# SCH__ESP32_NES__2022-10-13.net
KiCad netlist of a schematic drawn in EasyEDA
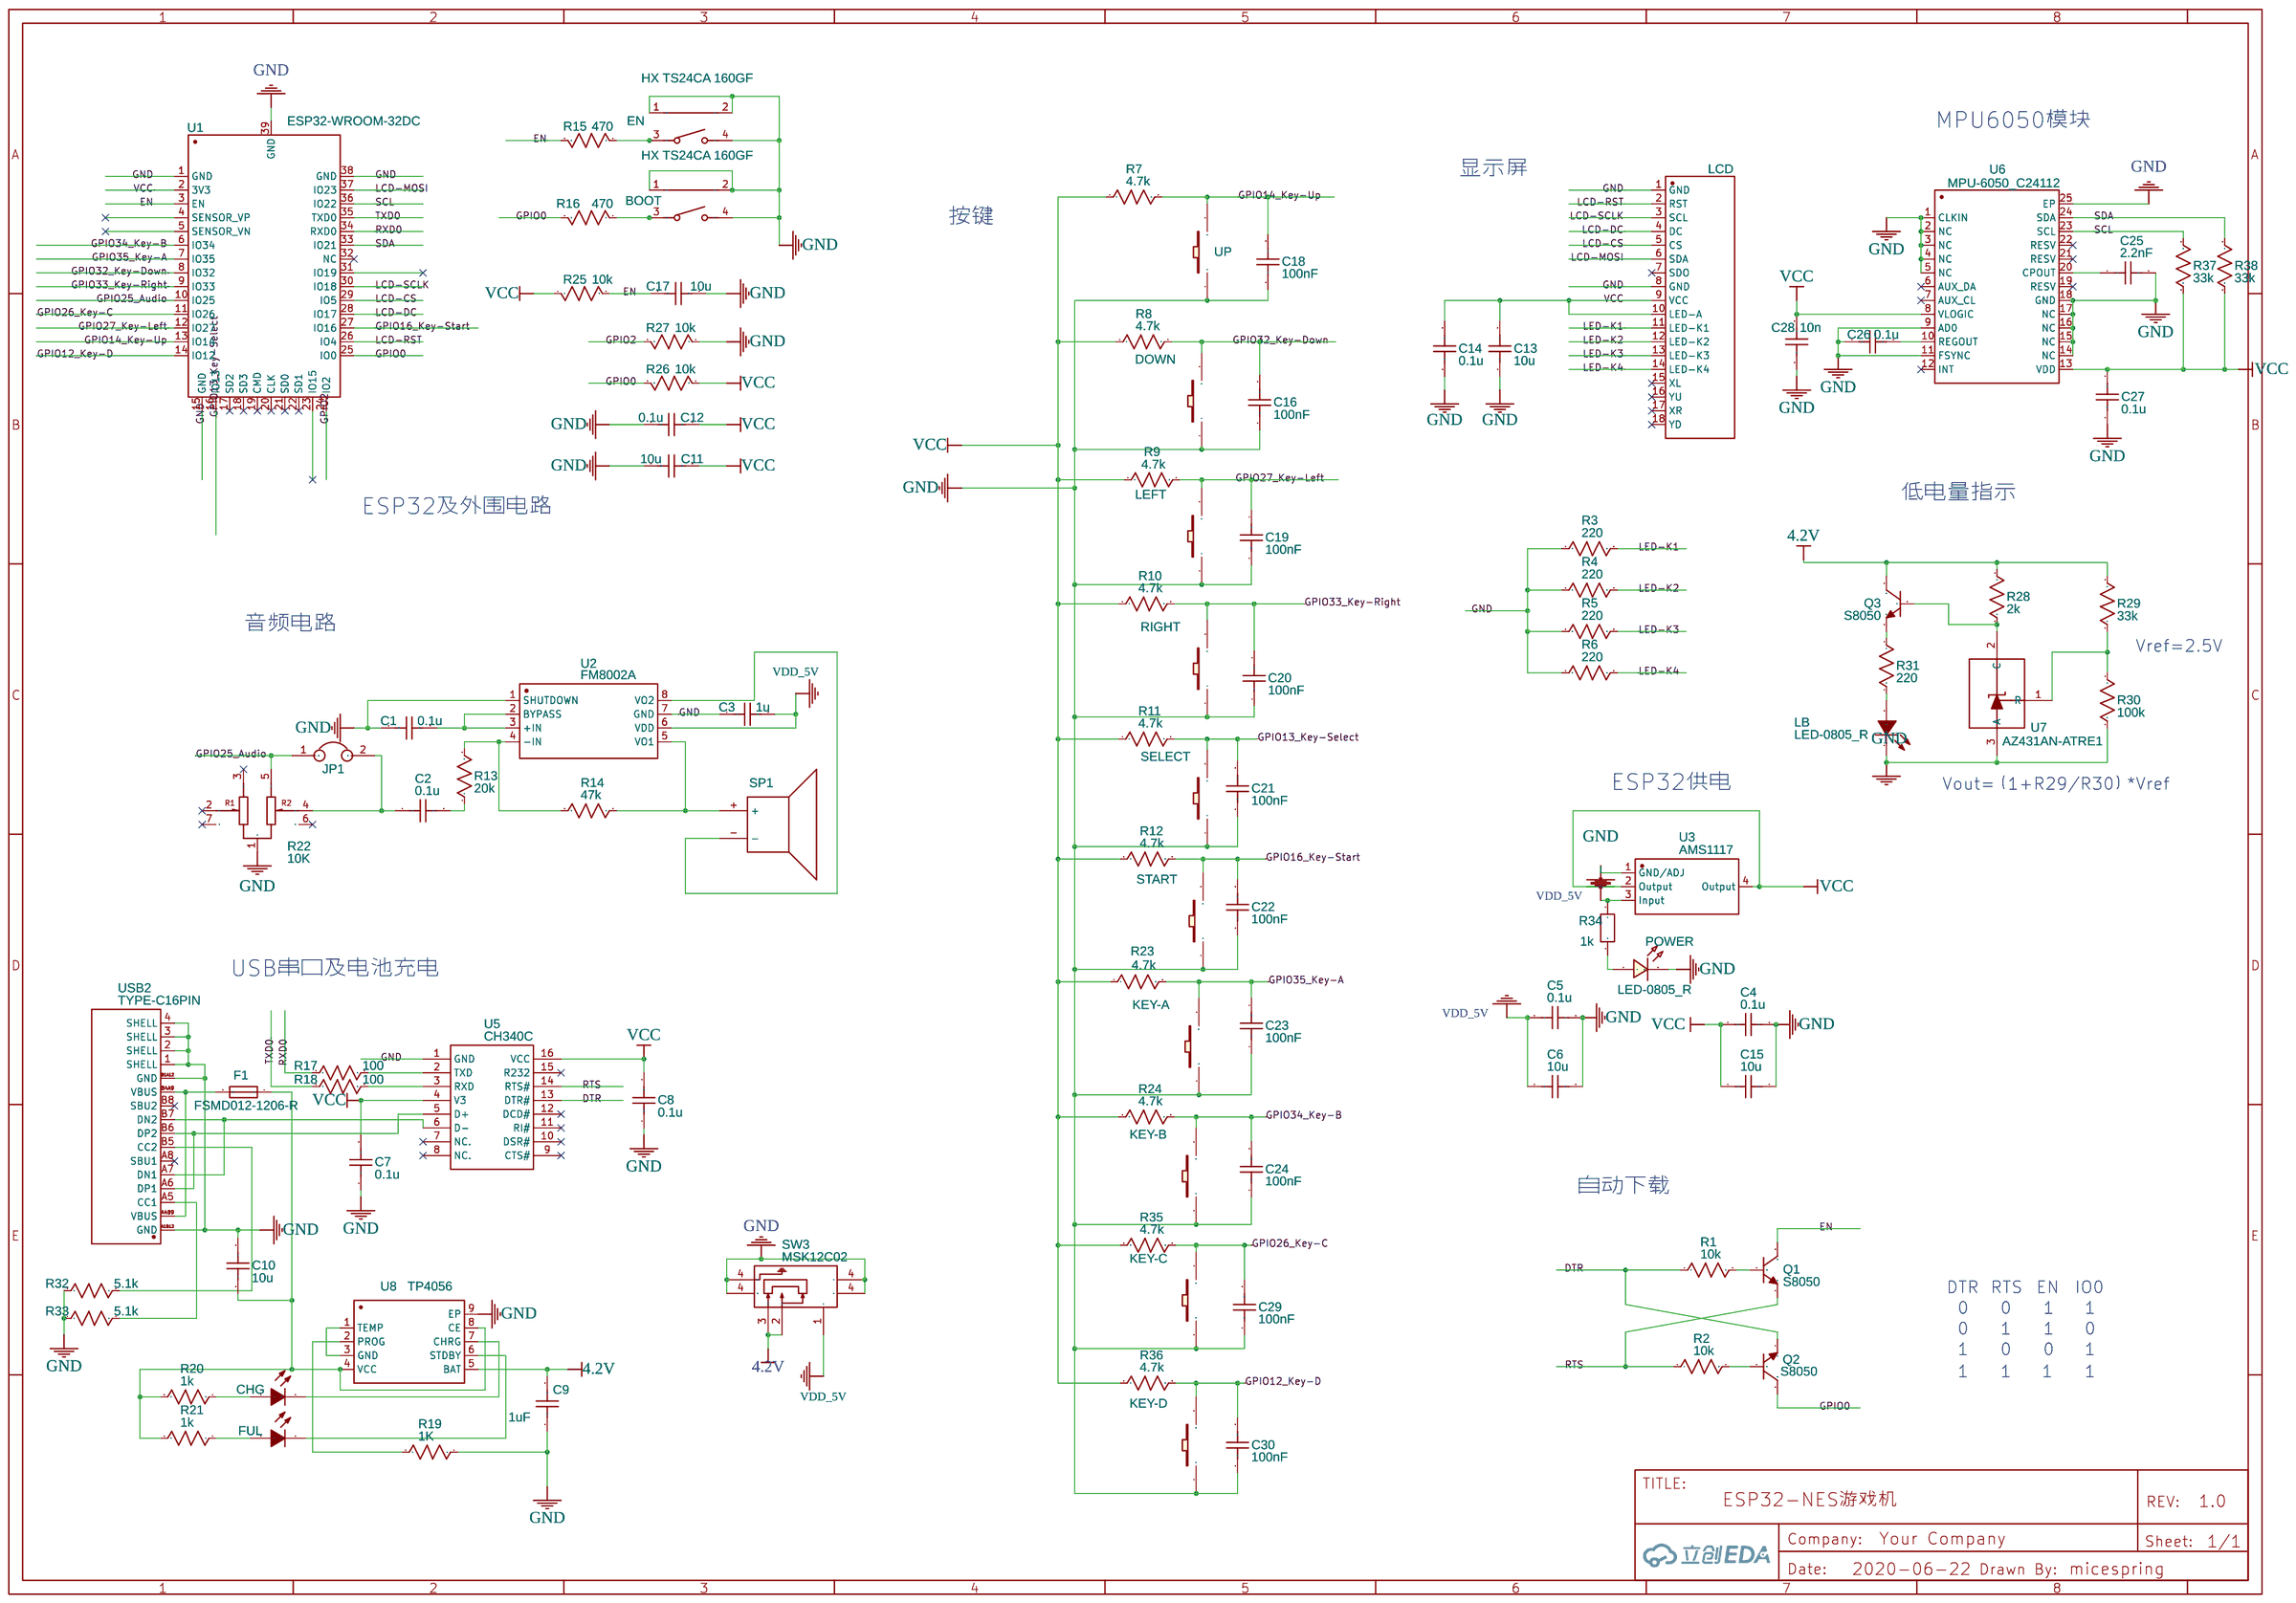
[diagram p0: 主板]
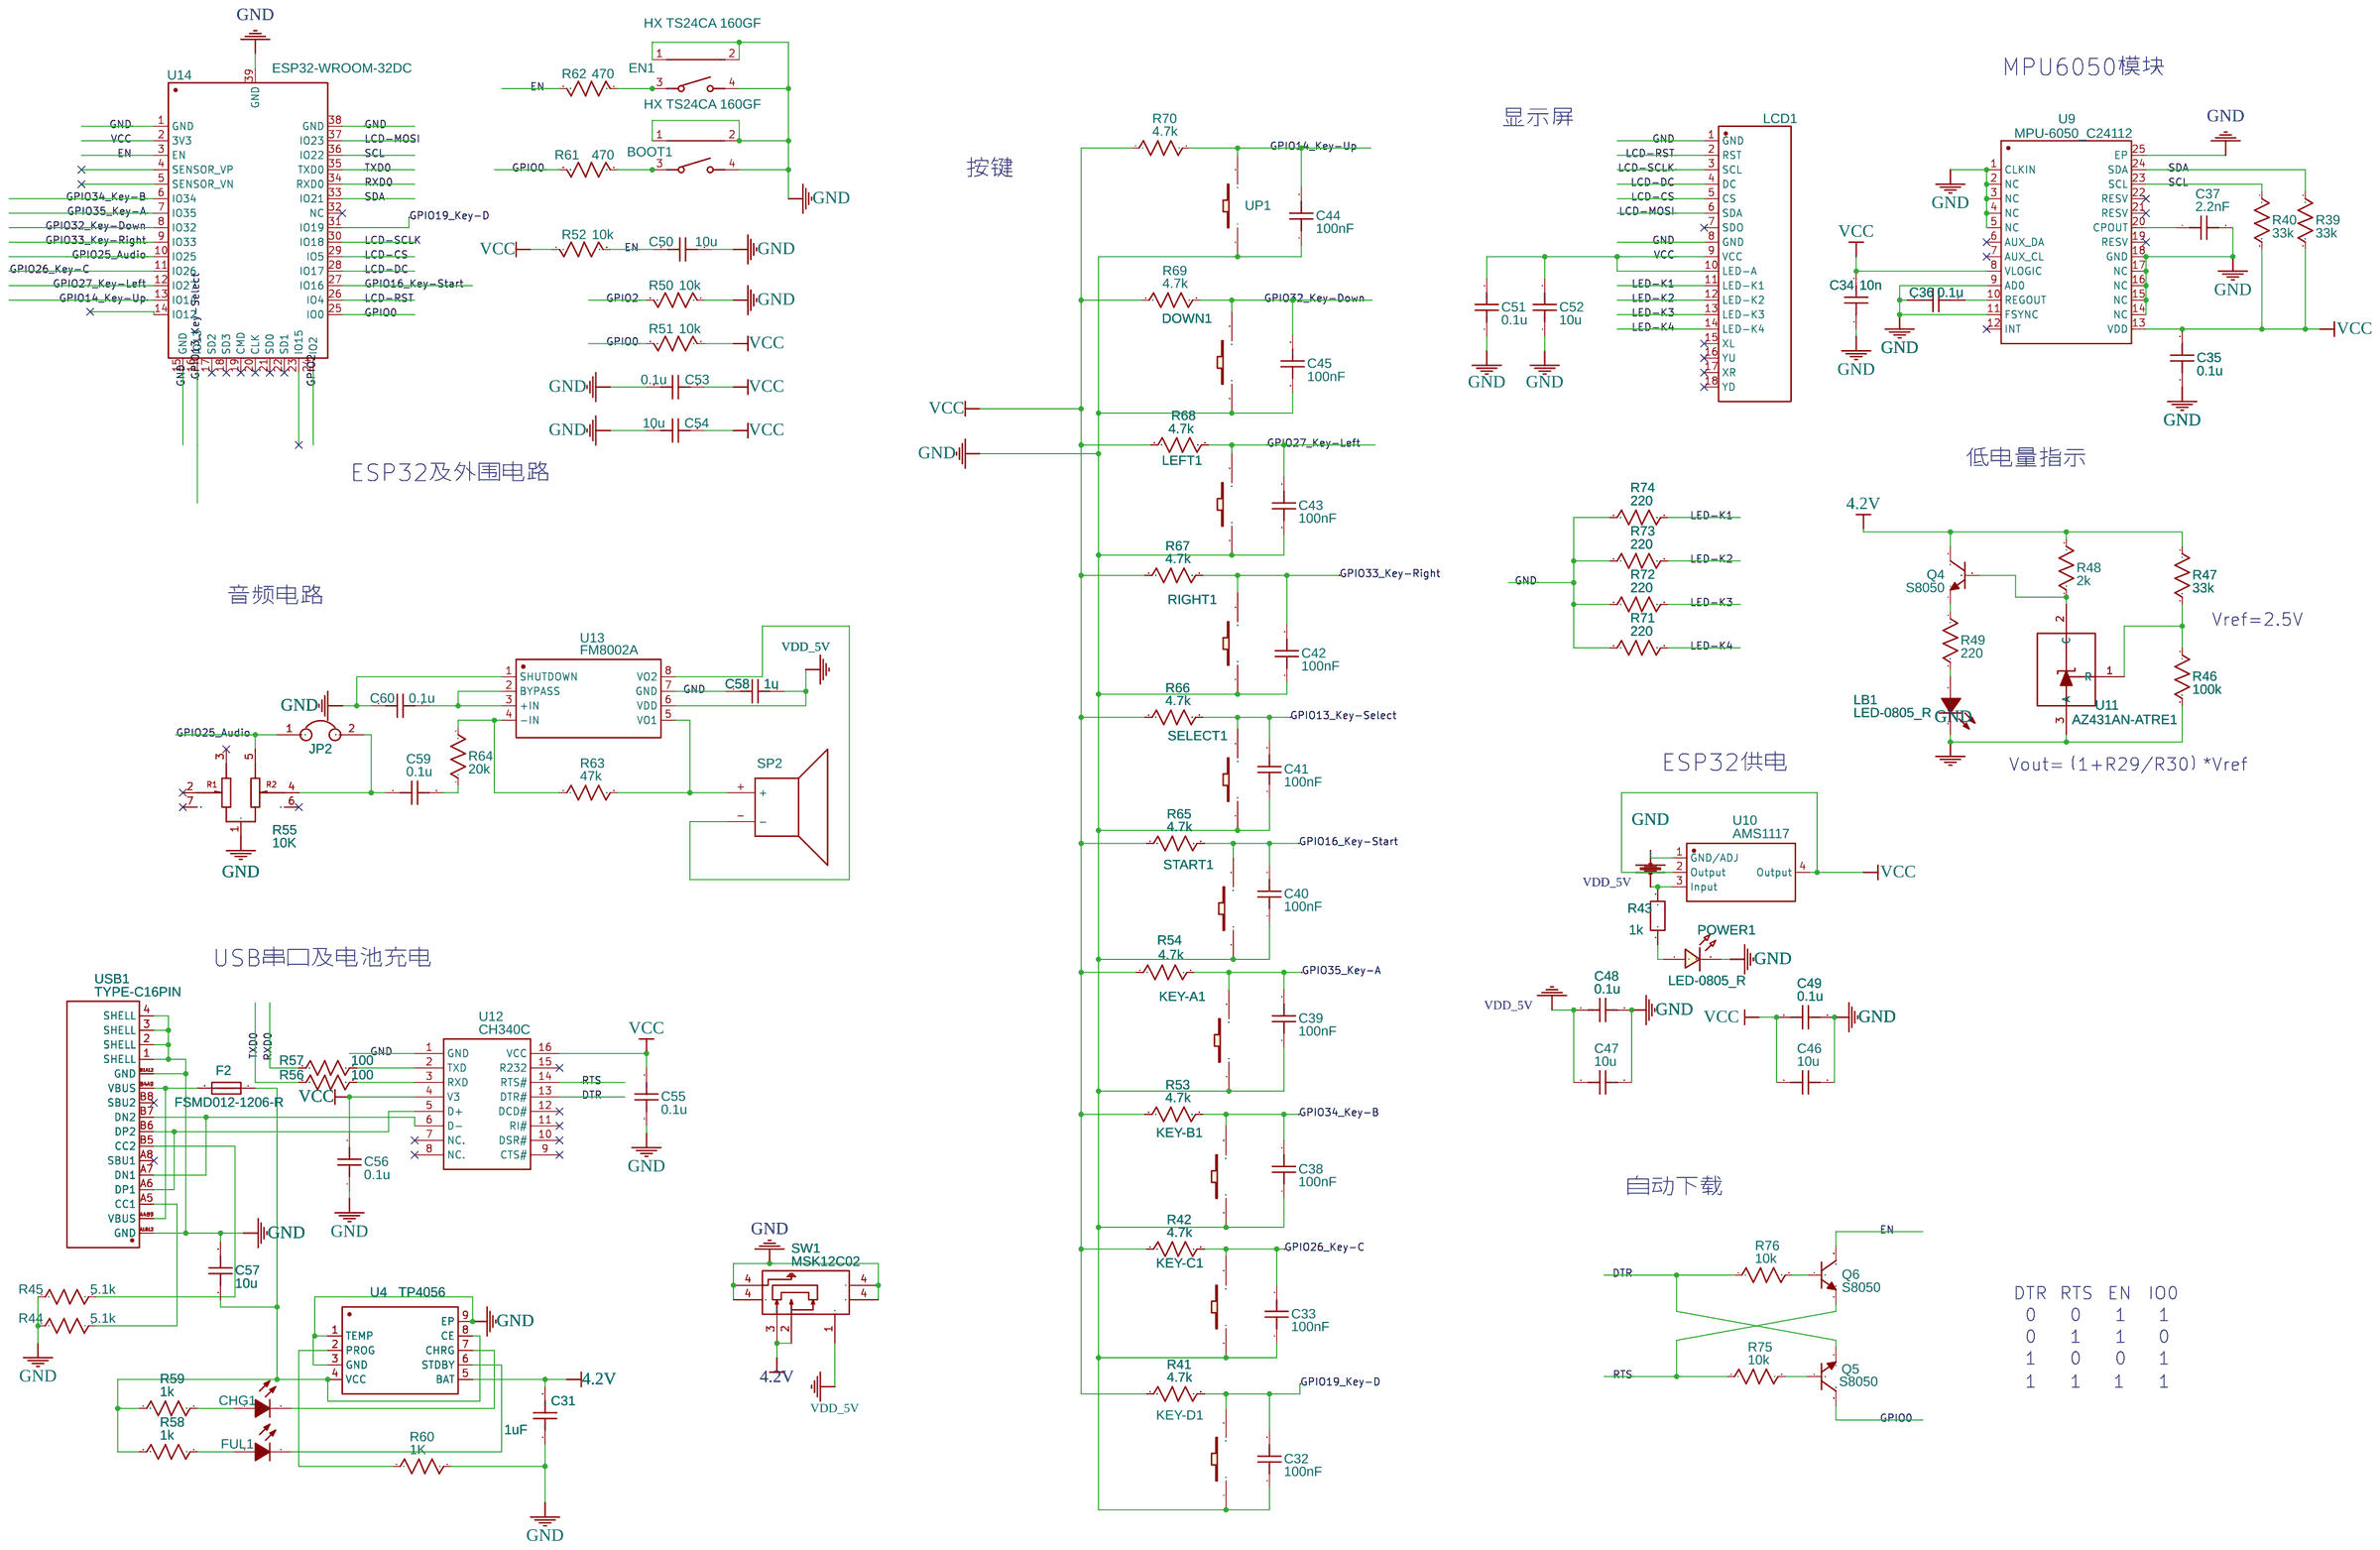
[diagram p1: 新主板]

(export (version "E")
  (design (tool "Eeschema 10.0.6"))
  (components
    (comp (ref "BOOT")
      (value "HX TS24CA 160GF")
      (fields
        (field (name "BOM_Manufacturer Part") "HX TS24CA 160gf")
        (field (name "BOM_Supplier Part") "C5143620")
      )
      (libsource (lib "") (part "HX TS24CA 160GF_1"))
    )
    (comp (ref "C1")
      (value "0.1u")
      (fields
        (field (name "BOM_Manufacturer Part") "TCC0805X7R104K500DT")
        (field (name "BOM_Supplier Part") "C282732")
      )
      (libsource (lib "") (part "C_0805_US_2"))
    )
    (comp (ref "C2")
      (value "0.1u")
      (fields
        (field (name "BOM_Manufacturer Part") "TCC0805X7R104K500DT")
        (field (name "BOM_Supplier Part") "C282732")
      )
      (libsource (lib "") (part "C_0805_US_2"))
    )
    (comp (ref "C3")
      (value "1u")
      (fields
        (field (name "BOM_Manufacturer Part") "0805B105K250NT")
        (field (name "BOM_Supplier Part") "C89190")
      )
      (libsource (lib "") (part "C_0805_US_2"))
    )
    (comp (ref "C4") (value "0.1u") (libsource (lib "") (part "C_0805_US_2")))
    (comp (ref "C5") (value "0.1u") (libsource (lib "") (part "C_0805_US_2")))
    (comp (ref "C6") (value "10u") (libsource (lib "") (part "C_0603_US_1")))
    (comp (ref "C7")
      (value "0.1u")
      (fields
        (field (name "BOM_Manufacturer Part") "TCC0805X7R104K500DT")
        (field (name "BOM_Supplier Part") "C282732")
      )
      (libsource (lib "") (part "C_0805_US_1"))
    )
    (comp (ref "C8")
      (value "0.1u")
      (fields
        (field (name "BOM_Manufacturer Part") "TCC0805X7R104K500DT")
        (field (name "BOM_Supplier Part") "C282732")
      )
      (libsource (lib "") (part "C_0805_US_1"))
    )
    (comp (ref "C9") (value "1uF") (libsource (lib "") (part "C_0603_US")))
    (comp (ref "C10")
      (value "10u")
      (fields
        (field (name "BOM_Manufacturer Part") "CL31A106KAHNNNE")
        (field (name "BOM_Supplier Part") "C9807")
      )
      (libsource (lib "") (part "Cap_1206_US"))
    )
    (comp (ref "C11")
      (value "10u")
      (fields
        (field (name "BOM_Manufacturer Part") "CL31A106KAHNNNE")
        (field (name "BOM_Supplier Part") "C9807")
      )
      (libsource (lib "") (part "C_0805_US"))
    )
    (comp (ref "C12")
      (value "0.1u")
      (fields
        (field (name "BOM_Manufacturer Part") "TCC0805X7R104K500DT")
        (field (name "BOM_Supplier Part") "C282732")
      )
      (libsource (lib "") (part "C_0805_US"))
    )
    (comp (ref "C13")
      (value "10u")
      (fields
        (field (name "BOM_Manufacturer Part") "CC0805KRX5R6BB106")
        (field (name "BOM_Supplier Part") "C272880")
      )
      (libsource (lib "") (part "Cap_0805_US"))
    )
    (comp (ref "C14")
      (value "0.1u")
      (fields
        (field (name "BOM_Manufacturer Part") "TCC0805X7R104K500DT")
        (field (name "BOM_Supplier Part") "C282732")
      )
      (libsource (lib "") (part "Cap_0805_US"))
    )
    (comp (ref "C15") (value "10u") (libsource (lib "") (part "C_0603_US_1")))
    (comp (ref "C16") (value "100nF") (libsource (lib "") (part "C_0603_US")))
    (comp (ref "C17")
      (value "10u")
      (fields
        (field (name "BOM_Manufacturer Part") "TCC0805X7R104K500DT")
        (field (name "BOM_Supplier Part") "C282732")
      )
      (libsource (lib "") (part "C_0805_US_3"))
    )
    (comp (ref "C18") (value "100nF") (libsource (lib "") (part "C_0603_US")))
    (comp (ref "C19") (value "100nF") (libsource (lib "") (part "C_0603_US_2")))
    (comp (ref "C20") (value "100nF") (libsource (lib "") (part "C_0603_US")))
    (comp (ref "C21") (value "100nF") (libsource (lib "") (part "C_0603_US")))
    (comp (ref "C22") (value "100nF") (libsource (lib "") (part "C_0603_US")))
    (comp (ref "C23") (value "100nF") (libsource (lib "") (part "C_0603_US")))
    (comp (ref "C24") (value "100nF") (libsource (lib "") (part "C_0603_US")))
    (comp (ref "C25") (value "2.2nF") (libsource (lib "") (part "C_0603_US_1")))
    (comp (ref "C26") (value "0.1u") (libsource (lib "") (part "C_0603_US_1")))
    (comp (ref "C27") (value "0.1u") (libsource (lib "") (part "C_0603_US")))
    (comp (ref "C28") (value "10n") (libsource (lib "") (part "C_0603_US")))
    (comp (ref "C29") (value "100nF") (libsource (lib "") (part "C_0603_US")))
    (comp (ref "C30") (value "100nF") (libsource (lib "") (part "C_0603_US")))
    (comp (ref "CHG")
      (value "17-21/BHC-XL2M2TY/3T")
      (fields (field (name "BOM_Supplier Part") "C72035"))
      (libsource (lib "") (part "Unknown_195_195"))
    )
    (comp (ref "DOWN")
      (value "K2-1817UQ-C4SW-01")
      (fields (field (name "BOM_Supplier Part") "C128939"))
      (libsource (lib "") (part "K2-1817UQ-C4SW-01_1"))
    )
    (comp (ref "EN")
      (value "HX TS24CA 160GF")
      (fields
        (field (name "BOM_Manufacturer Part") "HX TS24CA 160gf")
        (field (name "BOM_Supplier Part") "C5143620")
      )
      (libsource (lib "") (part "HX TS24CA 160GF"))
    )
    (comp (ref "F1")
      (value "FSMD012-1206-R")
      (fields (field (name "BOM_Supplier Part") "C220144"))
      (libsource (lib "") (part "FSMD012-1206-R"))
    )
    (comp (ref "FUL")
      (value "17-21/BHC-XL2M2TY/3T")
      (fields
        (field (name "BOM_Manufacturer Part") "FC-2012UGK-520D5")
        (field (name "BOM_Supplier Part") "C84260")
      )
      (libsource (lib "") (part "Unknown_195_225"))
    )
    (comp (ref "JP1") (value "JUMPER") (libsource (lib "") (part "JUMPER")))
    (comp (ref "KEY-A")
      (value "K2-1817UQ-C4SW-01")
      (fields (field (name "BOM_Supplier Part") "C128939"))
      (libsource (lib "") (part "K2-1817UQ-C4SW-01_2"))
    )
    (comp (ref "KEY-B")
      (value "K2-1817UQ-C4SW-01")
      (fields (field (name "BOM_Supplier Part") "C128939"))
      (libsource (lib "") (part "K2-1817UQ-C4SW-01_4"))
    )
    (comp (ref "KEY-C")
      (value "K2-1817UQ-C4SW-01")
      (fields (field (name "BOM_Supplier Part") "C128939"))
      (libsource (lib "") (part "K2-1817UQ-C4SW-01_5"))
    )
    (comp (ref "KEY-D")
      (value "K2-1817UQ-C4SW-01")
      (fields (field (name "BOM_Supplier Part") "C128939"))
      (libsource (lib "") (part "K2-1817UQ-C4SW-01_8"))
    )
    (comp (ref "LB")
      (value "LED-0805_R")
      (fields
        (field (name "BOM_Manufacturer Part") "17-21SURC/S530-A3/TR8")
        (field (name "BOM_Supplier Part") "C72037")
      )
      (libsource (lib "") (part "LED-0805_R"))
    )
    (comp (ref "LCD")
      (value "TFT_2.4_18P_SPI_ILI9341_240X320_65K_S")
      (libsource (lib "") (part "TFT_2.4_18P_SPI_ILI9341_240X320_65K_S"))
    )
    (comp (ref "LEFT")
      (value "K2-1817UQ-C4SW-01")
      (fields (field (name "BOM_Supplier Part") "C128939"))
      (libsource (lib "") (part "K2-1817UQ-C4SW-01_7"))
    )
    (comp (ref "POWER")
      (value "LED-0805_R")
      (fields
        (field (name "BOM_Manufacturer Part") "17-21SURC/S530-A3/TR8")
        (field (name "BOM_Supplier Part") "C72037")
      )
      (libsource (lib "") (part "LED-0805_R_1"))
    )
    (comp (ref "Q1")
      (value "S8050")
      (fields
        (field (name "BOM_Manufacturer Part") "2n3904S-RTK/PS")
        (field (name "BOM_Supplier Part") "C18536")
      )
      (libsource (lib "") (part "2N3904(SOT-23)_1"))
    )
    (comp (ref "Q2")
      (value "S8050")
      (fields
        (field (name "BOM_Manufacturer Part") "2n3904S-RTK/PS")
        (field (name "BOM_Supplier Part") "C18536")
      )
      (libsource (lib "") (part "2N3904(SOT-23)_2"))
    )
    (comp (ref "Q3")
      (value "S8050")
      (fields
        (field (name "BOM_Manufacturer Part") "2n3904S-RTK/PS")
        (field (name "BOM_Supplier Part") "C18536")
      )
      (libsource (lib "") (part "2N3904(SOT-23)"))
    )
    (comp (ref "R1")
      (value "10k")
      (fields
        (field (name "BOM_Manufacturer Part") "RTT051002FTP")
        (field (name "BOM_Supplier Part") "C103904")
      )
      (libsource (lib "") (part "R_0805_US_1"))
    )
    (comp (ref "R2")
      (value "10k")
      (fields
        (field (name "BOM_Manufacturer Part") "RTT051002FTP")
        (field (name "BOM_Supplier Part") "C103904")
      )
      (libsource (lib "") (part "R_0805_US_1"))
    )
    (comp (ref "R3")
      (value "220")
      (fields
        (field (name "BOM_Manufacturer Part") "RC0805FR-07220RL")
        (field (name "BOM_Supplier Part") "C114519")
      )
      (libsource (lib "") (part "R_0805_US_1"))
    )
    (comp (ref "R4")
      (value "220")
      (fields
        (field (name "BOM_Manufacturer Part") "RC0805FR-07220RL")
        (field (name "BOM_Supplier Part") "C114519")
      )
      (libsource (lib "") (part "R_0805_US_1"))
    )
    (comp (ref "R5")
      (value "220")
      (fields
        (field (name "BOM_Manufacturer Part") "RC0805FR-07220RL")
        (field (name "BOM_Supplier Part") "C114519")
      )
      (libsource (lib "") (part "R_0805_US_1"))
    )
    (comp (ref "R6")
      (value "220")
      (fields
        (field (name "BOM_Manufacturer Part") "RC0805FR-07220RL")
        (field (name "BOM_Supplier Part") "C114519")
      )
      (libsource (lib "") (part "R_0805_US_1"))
    )
    (comp (ref "R7")
      (value "4.7k")
      (fields
        (field (name "BOM_Manufacturer Part") "0805W8F4701T5E")
        (field (name "BOM_Supplier Part") "C17673")
      )
      (libsource (lib "") (part "R_0805_US_1"))
    )
    (comp (ref "R8")
      (value "4.7k")
      (fields
        (field (name "BOM_Manufacturer Part") "0805W8F4701T5E")
        (field (name "BOM_Supplier Part") "C17673")
      )
      (libsource (lib "") (part "R_0805_US_1"))
    )
    (comp (ref "R9")
      (value "4.7k")
      (fields
        (field (name "BOM_Manufacturer Part") "0805W8F4701T5E")
        (field (name "BOM_Supplier Part") "C17673")
      )
      (libsource (lib "") (part "R_0805_US_1"))
    )
    (comp (ref "R10")
      (value "4.7k")
      (fields
        (field (name "BOM_Manufacturer Part") "0805W8F4701T5E")
        (field (name "BOM_Supplier Part") "C17673")
      )
      (libsource (lib "") (part "R_0805_US_1"))
    )
    (comp (ref "R11")
      (value "4.7k")
      (fields
        (field (name "BOM_Manufacturer Part") "0805W8F4701T5E")
        (field (name "BOM_Supplier Part") "C17673")
      )
      (libsource (lib "") (part "R_0805_US_1"))
    )
    (comp (ref "R12")
      (value "4.7k")
      (fields
        (field (name "BOM_Manufacturer Part") "0805W8F4701T5E")
        (field (name "BOM_Supplier Part") "C17673")
      )
      (libsource (lib "") (part "R_0805_US_1"))
    )
    (comp (ref "R13")
      (value "20k")
      (fields
        (field (name "BOM_Manufacturer Part") "RS-05K2002FT")
        (field (name "BOM_Supplier Part") "C136576")
      )
      (libsource (lib "") (part "R_0805_US_3"))
    )
    (comp (ref "R14")
      (value "47k")
      (fields
        (field (name "BOM_Manufacturer Part") "RS-05K4702FT")
        (field (name "BOM_Supplier Part") "C136580")
      )
      (libsource (lib "") (part "R_0805_US_1"))
    )
    (comp (ref "R15")
      (value "470")
      (fields
        (field (name "BOM_Manufacturer Part") "RC0805FR-07470RL")
        (field (name "BOM_Supplier Part") "C114564")
      )
      (libsource (lib "") (part "R_0805_US"))
    )
    (comp (ref "R16")
      (value "470")
      (fields
        (field (name "BOM_Manufacturer Part") "RC0805FR-07470RL")
        (field (name "BOM_Supplier Part") "C114564")
      )
      (libsource (lib "") (part "R_0805_US"))
    )
    (comp (ref "R17")
      (value "100")
      (fields
        (field (name "BOM_Manufacturer Part") "CR0805F81000G")
        (field (name "BOM_Supplier Part") "C101403")
      )
      (libsource (lib "") (part "R_0805_US_1"))
    )
    (comp (ref "R18")
      (value "100")
      (fields
        (field (name "BOM_Manufacturer Part") "CR0805F81000G")
        (field (name "BOM_Supplier Part") "C101403")
      )
      (libsource (lib "") (part "R_0805_US_1"))
    )
    (comp (ref "R19")
      (value "1K")
      (fields
        (field (name "BOM_Manufacturer Part") "RS-05K3301FT")
        (field (name "BOM_Supplier Part") "C294703")
      )
      (libsource (lib "") (part "Res_0805(1/8W)_US_1"))
    )
    (comp (ref "R20")
      (value "1k")
      (fields
        (field (name "BOM_Manufacturer Part") "0805W8F1001T5E")
        (field (name "BOM_Supplier Part") "C17513")
      )
      (libsource (lib "") (part "Res_0805(1/8W)_US_2"))
    )
    (comp (ref "R21")
      (value "1k")
      (fields
        (field (name "BOM_Manufacturer Part") "0805W8F1001T5E")
        (field (name "BOM_Supplier Part") "C17513")
      )
      (libsource (lib "") (part "Res_0805(1/8W)_US_2"))
    )
    (comp (ref "R22")
      (value "10K")
      (fields
        (field (name "BOM_Manufacturer Part") "RK10J12E002L")
        (field (name "BOM_Supplier Part") "C231765")
      )
      (libsource (lib "") (part "RK10J12E002L"))
    )
    (comp (ref "R23")
      (value "4.7k")
      (fields
        (field (name "BOM_Manufacturer Part") "0805W8F4701T5E")
        (field (name "BOM_Supplier Part") "C17673")
      )
      (libsource (lib "") (part "R_0805_US_1"))
    )
    (comp (ref "R24")
      (value "4.7k")
      (fields
        (field (name "BOM_Manufacturer Part") "0805W8F4701T5E")
        (field (name "BOM_Supplier Part") "C17673")
      )
      (libsource (lib "") (part "R_0805_US_1"))
    )
    (comp (ref "R25")
      (value "10k")
      (fields
        (field (name "BOM_Manufacturer Part") "RTT051002FTP")
        (field (name "BOM_Supplier Part") "C103904")
      )
      (libsource (lib "") (part "R_0805_US_2"))
    )
    (comp (ref "R26")
      (value "10k")
      (fields
        (field (name "BOM_Manufacturer Part") "RTT051002FTP")
        (field (name "BOM_Supplier Part") "C103904")
      )
      (libsource (lib "") (part "R_0805_US"))
    )
    (comp (ref "R27")
      (value "10k")
      (fields
        (field (name "BOM_Manufacturer Part") "RTT051002FTP")
        (field (name "BOM_Supplier Part") "C103904")
      )
      (libsource (lib "") (part "R_0805_US"))
    )
    (comp (ref "R28")
      (value "2k")
      (fields
        (field (name "BOM_Manufacturer Part") "0805W8F2001T5E")
        (field (name "BOM_Supplier Part") "C17604")
      )
      (libsource (lib "") (part "Res_0805(1/8W)_US"))
    )
    (comp (ref "R29")
      (value "33k")
      (fields
        (field (name "BOM_Manufacturer Part") "RS-05K3302FT")
        (field (name "BOM_Supplier Part") "C139883")
      )
      (libsource (lib "") (part "Res_0805(1/8W)_US"))
    )
    (comp (ref "R30")
      (value "100k")
      (fields
        (field (name "BOM_Manufacturer Part") "0805W8F1003T5E")
        (field (name "BOM_Supplier Part") "C149504")
      )
      (libsource (lib "") (part "Res_0805(1/8W)_US"))
    )
    (comp (ref "R31")
      (value "220")
      (fields
        (field (name "BOM_Manufacturer Part") "RC0805FR-07220RL")
        (field (name "BOM_Supplier Part") "C114519")
      )
      (libsource (lib "") (part "Res_0805(1/8W)_US"))
    )
    (comp (ref "R32")
      (value "5.1k")
      (fields
        (field (name "BOM_Manufacturer Part") "CR0805F81000G")
        (field (name "BOM_Supplier Part") "C101403")
      )
      (libsource (lib "") (part "R_0805_US_1"))
    )
    (comp (ref "R33")
      (value "5.1k")
      (fields
        (field (name "BOM_Manufacturer Part") "CR0805F81000G")
        (field (name "BOM_Supplier Part") "C101403")
      )
      (libsource (lib "") (part "R_0805_US_1"))
    )
    (comp (ref "R34") (value "1k") (libsource (lib "") (part "R_0805_EU")))
    (comp (ref "R35")
      (value "4.7k")
      (fields
        (field (name "BOM_Manufacturer Part") "0805W8F4701T5E")
        (field (name "BOM_Supplier Part") "C17673")
      )
      (libsource (lib "") (part "R_0805_US_1"))
    )
    (comp (ref "R36")
      (value "4.7k")
      (fields
        (field (name "BOM_Manufacturer Part") "0805W8F4701T5E")
        (field (name "BOM_Supplier Part") "C17673")
      )
      (libsource (lib "") (part "R_0805_US_1"))
    )
    (comp (ref "R37")
      (value "33k")
      (fields
        (field (name "BOM_Manufacturer Part") "RS-05K3302FT")
        (field (name "BOM_Supplier Part") "C139883")
      )
      (libsource (lib "") (part "Res_0805(1/8W)_US"))
    )
    (comp (ref "R38")
      (value "33k")
      (fields
        (field (name "BOM_Manufacturer Part") "RS-05K3302FT")
        (field (name "BOM_Supplier Part") "C139883")
      )
      (libsource (lib "") (part "Res_0805(1/8W)_US"))
    )
    (comp (ref "RIGHT")
      (value "K2-1817UQ-C4SW-01")
      (fields (field (name "BOM_Supplier Part") "C128939"))
      (libsource (lib "") (part "K2-1817UQ-C4SW-01_6"))
    )
    (comp (ref "SELECT")
      (value "K2-1817UQ-C4SW-01")
      (fields (field (name "BOM_Supplier Part") "C128939"))
      (libsource (lib "") (part "K2-1817UQ-C4SW-01_9"))
    )
    (comp (ref "SP1")
      (value "SPEAKER-FS-2308-P9.2")
      (fields (field (name "BOM_Supplier Part") "C482322"))
      (libsource (lib "") (part "SPEAKER-FS-2308-P9.2"))
    )
    (comp (ref "START")
      (value "K2-1817UQ-C4SW-01")
      (fields (field (name "BOM_Supplier Part") "C128939"))
      (libsource (lib "") (part "K2-1817UQ-C4SW-01_3"))
    )
    (comp (ref "SW3")
      (value "MSK12C02")
      (fields (field (name "BOM_Supplier Part") "C431540"))
      (libsource (lib "") (part "MSK12C02"))
    )
    (comp (ref "U1")
      (value "ESP32-WROOM-32DC")
      (fields (field (name "BOM_Supplier Part") "C473013"))
      (libsource (lib "") (part "ESP32-WROOM-32DC"))
    )
    (comp (ref "U2")
      (value "FM8002A")
      (fields (field (name "BOM_Supplier Part") "C94625"))
      (libsource (lib "") (part "FM8002A"))
    )
    (comp (ref "U3")
      (value "AMS1117")
      (fields
        (field (name "BOM_Manufacturer Part") "AMS1117-3.3")
        (field (name "BOM_Supplier Part") "C369933")
      )
      (libsource (lib "") (part "AMS1117-3.3_C369933"))
    )
    (comp (ref "U5")
      (value "CH340C")
      (fields (field (name "BOM_Supplier Part") "C84681"))
      (libsource (lib "") (part "CH340C"))
    )
    (comp (ref "U6")
      (value "MPU-6050_C24112")
      (fields (field (name "BOM_Manufacturer Part") "MPU-6050") (field (name "BOM_Supplier Part") "C24112"))
      (libsource (lib "") (part "MPU-6050_C24112"))
    )
    (comp (ref "U7")
      (value "AZ431AN-ATRE1")
      (fields (field (name "BOM_Supplier Part") "C84138"))
      (libsource (lib "") (part "AZ431AN-ATRE1"))
    )
    (comp (ref "U8")
      (value "TP4056")
      (fields (field (name "BOM_Supplier Part") "C725790"))
      (libsource (lib "") (part "TP4056_C725790"))
    )
    (comp (ref "UP")
      (value "K2-1817UQ-C4SW-01")
      (fields (field (name "BOM_Supplier Part") "C128939"))
      (libsource (lib "") (part "K2-1817UQ-C4SW-01"))
    )
    (comp (ref "USB2")
      (value "TYPE-C16PIN")
      (fields (field (name "BOM_Supplier Part") "C393939"))
      (libsource (lib "") (part "TYPE-C16PIN"))
    )
    (comp (ref "BOOT1")
      (value "HX TS24CA 160GF")
      (fields
        (field (name "BOM_Manufacturer Part") "HX TS24CA 160gf")
        (field (name "BOM_Supplier Part") "C5143620")
      )
      (libsource (lib "") (part "HX TS24CA 160GF"))
    )
    (comp (ref "C31") (value "1uF") (libsource (lib "") (part "C_0603_US_2")))
    (comp (ref "C32") (value "100nF") (libsource (lib "") (part "C_0603_US_2")))
    (comp (ref "C33") (value "100nF") (libsource (lib "") (part "C_0603_US_2")))
    (comp (ref "C34") (value "10n") (libsource (lib "") (part "C_0603_US_2")))
    (comp (ref "C35") (value "0.1u") (libsource (lib "") (part "C_0603_US_2")))
    (comp (ref "C36") (value "0.1u") (libsource (lib "") (part "C_0603_US")))
    (comp (ref "C37") (value "2.2nF") (libsource (lib "") (part "C_0603_US")))
    (comp (ref "C38") (value "100nF") (libsource (lib "") (part "C_0603_US_2")))
    (comp (ref "C39") (value "100nF") (libsource (lib "") (part "C_0603_US_2")))
    (comp (ref "C40") (value "100nF") (libsource (lib "") (part "C_0603_US_2")))
    (comp (ref "C41") (value "100nF") (libsource (lib "") (part "C_0603_US_2")))
    (comp (ref "C42") (value "100nF") (libsource (lib "") (part "C_0603_US_2")))
    (comp (ref "C43") (value "100nF") (libsource (lib "") (part "C_0603_US_1")))
    (comp (ref "C44") (value "100nF") (libsource (lib "") (part "C_0603_US_2")))
    (comp (ref "C45") (value "100nF") (libsource (lib "") (part "C_0603_US_2")))
    (comp (ref "C46") (value "10u") (libsource (lib "") (part "C_0603_US")))
    (comp (ref "C47") (value "10u") (libsource (lib "") (part "C_0603_US")))
    (comp (ref "C48") (value "0.1u") (libsource (lib "") (part "C_0805_US")))
    (comp (ref "C49") (value "0.1u") (libsource (lib "") (part "C_0805_US")))
    (comp (ref "C50")
      (value "10u")
      (fields
        (field (name "BOM_Manufacturer Part") "TCC0805X7R104K500DT")
        (field (name "BOM_Supplier Part") "C282732")
      )
      (libsource (lib "") (part "C_0805_US_1"))
    )
    (comp (ref "C51")
      (value "0.1u")
      (fields
        (field (name "BOM_Manufacturer Part") "TCC0805X7R104K500DT")
        (field (name "BOM_Supplier Part") "C282732")
      )
      (libsource (lib "") (part "Cap_0805_US"))
    )
    (comp (ref "C52")
      (value "10u")
      (fields
        (field (name "BOM_Manufacturer Part") "CC0805KRX5R6BB106")
        (field (name "BOM_Supplier Part") "C272880")
      )
      (libsource (lib "") (part "Cap_0805_US"))
    )
    (comp (ref "C53")
      (value "0.1u")
      (fields
        (field (name "BOM_Manufacturer Part") "TCC0805X7R104K500DT")
        (field (name "BOM_Supplier Part") "C282732")
      )
      (libsource (lib "") (part "C_0805_US_2"))
    )
    (comp (ref "C54")
      (value "10u")
      (fields
        (field (name "BOM_Manufacturer Part") "CL31A106KAHNNNE")
        (field (name "BOM_Supplier Part") "C9807")
      )
      (libsource (lib "") (part "C_0805_US_2"))
    )
    (comp (ref "C55")
      (value "0.1u")
      (fields
        (field (name "BOM_Manufacturer Part") "TCC0805X7R104K500DT")
        (field (name "BOM_Supplier Part") "C282732")
      )
      (libsource (lib "") (part "C_0805_US_3"))
    )
    (comp (ref "C56")
      (value "0.1u")
      (fields
        (field (name "BOM_Manufacturer Part") "TCC0805X7R104K500DT")
        (field (name "BOM_Supplier Part") "C282732")
      )
      (libsource (lib "") (part "C_0805_US_3"))
    )
    (comp (ref "C57")
      (value "10u")
      (fields
        (field (name "BOM_Manufacturer Part") "CL31A106KAHNNNE")
        (field (name "BOM_Supplier Part") "C9807")
      )
      (libsource (lib "") (part "Cap_1206_US"))
    )
    (comp (ref "C58")
      (value "1u")
      (fields
        (field (name "BOM_Manufacturer Part") "0805B105K250NT")
        (field (name "BOM_Supplier Part") "C89190")
      )
      (libsource (lib "") (part "C_0805_US"))
    )
    (comp (ref "C59")
      (value "0.1u")
      (fields
        (field (name "BOM_Manufacturer Part") "TCC0805X7R104K500DT")
        (field (name "BOM_Supplier Part") "C282732")
      )
      (libsource (lib "") (part "C_0805_US"))
    )
    (comp (ref "C60")
      (value "0.1u")
      (fields
        (field (name "BOM_Manufacturer Part") "TCC0805X7R104K500DT")
        (field (name "BOM_Supplier Part") "C282732")
      )
      (libsource (lib "") (part "C_0805_US"))
    )
    (comp (ref "CHG1")
      (value "17-21/BHC-XL2M2TY/3T")
      (fields (field (name "BOM_Supplier Part") "C72035"))
      (libsource (lib "") (part "Unknown_259_-143"))
    )
    (comp (ref "DOWN1")
      (value "K2-1817UQ-C4SW-01")
      (fields (field (name "BOM_Supplier Part") "C128939"))
      (libsource (lib "") (part "K2-1817UQ-C4SW-01_9"))
    )
    (comp (ref "EN1")
      (value "HX TS24CA 160GF")
      (fields
        (field (name "BOM_Manufacturer Part") "HX TS24CA 160gf")
        (field (name "BOM_Supplier Part") "C5143620")
      )
      (libsource (lib "") (part "HX TS24CA 160GF_1"))
    )
    (comp (ref "F2")
      (value "FSMD012-1206-R")
      (fields (field (name "BOM_Supplier Part") "C220144"))
      (libsource (lib "") (part "FSMD012-1206-R"))
    )
    (comp (ref "FUL1")
      (value "17-21/BHC-XL2M2TY/3T")
      (fields
        (field (name "BOM_Manufacturer Part") "FC-2012UGK-520D5")
        (field (name "BOM_Supplier Part") "C84260")
      )
      (libsource (lib "") (part "Unknown_259_-113"))
    )
    (comp (ref "JP2") (value "JUMPER") (libsource (lib "") (part "JUMPER")))
    (comp (ref "KEY-A1")
      (value "K2-1817UQ-C4SW-01")
      (fields (field (name "BOM_Supplier Part") "C128939"))
      (libsource (lib "") (part "K2-1817UQ-C4SW-01_8"))
    )
    (comp (ref "KEY-B1")
      (value "K2-1817UQ-C4SW-01")
      (fields (field (name "BOM_Supplier Part") "C128939"))
      (libsource (lib "") (part "K2-1817UQ-C4SW-01_4"))
    )
    (comp (ref "KEY-C1")
      (value "K2-1817UQ-C4SW-01")
      (fields (field (name "BOM_Supplier Part") "C128939"))
      (libsource (lib "") (part "K2-1817UQ-C4SW-01"))
    )
    (comp (ref "KEY-D1")
      (value "K2-1817UQ-C4SW-01")
      (fields (field (name "BOM_Supplier Part") "C128939"))
      (libsource (lib "") (part "K2-1817UQ-C4SW-01_5"))
    )
    (comp (ref "LB1")
      (value "LED-0805_R")
      (fields
        (field (name "BOM_Manufacturer Part") "17-21SURC/S530-A3/TR8")
        (field (name "BOM_Supplier Part") "C72037")
      )
      (libsource (lib "") (part "LED-0805_R"))
    )
    (comp (ref "LCD1")
      (value "TFT_2.4_18P_SPI_ILI9341_240X320_65K_S")
      (libsource (lib "") (part "TFT_2.4_18P_SPI_ILI9341_240X320_65K_S"))
    )
    (comp (ref "LEFT1")
      (value "K2-1817UQ-C4SW-01")
      (fields (field (name "BOM_Supplier Part") "C128939"))
      (libsource (lib "") (part "K2-1817UQ-C4SW-01_6"))
    )
    (comp (ref "POWER1")
      (value "LED-0805_R")
      (fields
        (field (name "BOM_Manufacturer Part") "17-21SURC/S530-A3/TR8")
        (field (name "BOM_Supplier Part") "C72037")
      )
      (libsource (lib "") (part "LED-0805_R_1"))
    )
    (comp (ref "Q4")
      (value "S8050")
      (fields
        (field (name "BOM_Manufacturer Part") "2n3904S-RTK/PS")
        (field (name "BOM_Supplier Part") "C18536")
      )
      (libsource (lib "") (part "2N3904(SOT-23)_1"))
    )
    (comp (ref "Q5")
      (value "S8050")
      (fields
        (field (name "BOM_Manufacturer Part") "2n3904S-RTK/PS")
        (field (name "BOM_Supplier Part") "C18536")
      )
      (libsource (lib "") (part "2N3904(SOT-23)_2"))
    )
    (comp (ref "Q6")
      (value "S8050")
      (fields
        (field (name "BOM_Manufacturer Part") "2n3904S-RTK/PS")
        (field (name "BOM_Supplier Part") "C18536")
      )
      (libsource (lib "") (part "2N3904(SOT-23)"))
    )
    (comp (ref "R39")
      (value "33k")
      (fields
        (field (name "BOM_Manufacturer Part") "RS-05K3302FT")
        (field (name "BOM_Supplier Part") "C139883")
      )
      (libsource (lib "") (part "Res_0805(1/8W)_US_1"))
    )
    (comp (ref "R40")
      (value "33k")
      (fields
        (field (name "BOM_Manufacturer Part") "RS-05K3302FT")
        (field (name "BOM_Supplier Part") "C139883")
      )
      (libsource (lib "") (part "Res_0805(1/8W)_US_1"))
    )
    (comp (ref "R41")
      (value "4.7k")
      (fields
        (field (name "BOM_Manufacturer Part") "0805W8F4701T5E")
        (field (name "BOM_Supplier Part") "C17673")
      )
      (libsource (lib "") (part "R_0805_US"))
    )
    (comp (ref "R42")
      (value "4.7k")
      (fields
        (field (name "BOM_Manufacturer Part") "0805W8F4701T5E")
        (field (name "BOM_Supplier Part") "C17673")
      )
      (libsource (lib "") (part "R_0805_US"))
    )
    (comp (ref "R43") (value "1k") (libsource (lib "") (part "R_0805_EU")))
    (comp (ref "R44")
      (value "5.1k")
      (fields
        (field (name "BOM_Manufacturer Part") "CR0805F81000G")
        (field (name "BOM_Supplier Part") "C101403")
      )
      (libsource (lib "") (part "R_0805_US"))
    )
    (comp (ref "R45")
      (value "5.1k")
      (fields
        (field (name "BOM_Manufacturer Part") "CR0805F81000G")
        (field (name "BOM_Supplier Part") "C101403")
      )
      (libsource (lib "") (part "R_0805_US"))
    )
    (comp (ref "R46")
      (value "100k")
      (fields
        (field (name "BOM_Manufacturer Part") "0805W8F1003T5E")
        (field (name "BOM_Supplier Part") "C149504")
      )
      (libsource (lib "") (part "Res_0805(1/8W)_US_1"))
    )
    (comp (ref "R47")
      (value "33k")
      (fields
        (field (name "BOM_Manufacturer Part") "RS-05K3302FT")
        (field (name "BOM_Supplier Part") "C139883")
      )
      (libsource (lib "") (part "Res_0805(1/8W)_US_1"))
    )
    (comp (ref "R48")
      (value "2k")
      (fields
        (field (name "BOM_Manufacturer Part") "0805W8F2001T5E")
        (field (name "BOM_Supplier Part") "C17604")
      )
      (libsource (lib "") (part "Res_0805(1/8W)_US_1"))
    )
    (comp (ref "R49")
      (value "220")
      (fields
        (field (name "BOM_Manufacturer Part") "RC0805FR-07220RL")
        (field (name "BOM_Supplier Part") "C114519")
      )
      (libsource (lib "") (part "Res_0805(1/8W)_US_1"))
    )
    (comp (ref "R50")
      (value "10k")
      (fields
        (field (name "BOM_Manufacturer Part") "RTT051002FTP")
        (field (name "BOM_Supplier Part") "C103904")
      )
      (libsource (lib "") (part "R_0805_US_2"))
    )
    (comp (ref "R51")
      (value "10k")
      (fields
        (field (name "BOM_Manufacturer Part") "RTT051002FTP")
        (field (name "BOM_Supplier Part") "C103904")
      )
      (libsource (lib "") (part "R_0805_US_2"))
    )
    (comp (ref "R52")
      (value "10k")
      (fields
        (field (name "BOM_Manufacturer Part") "RTT051002FTP")
        (field (name "BOM_Supplier Part") "C103904")
      )
      (libsource (lib "") (part "R_0805_US_1"))
    )
    (comp (ref "R53")
      (value "4.7k")
      (fields
        (field (name "BOM_Manufacturer Part") "0805W8F4701T5E")
        (field (name "BOM_Supplier Part") "C17673")
      )
      (libsource (lib "") (part "R_0805_US"))
    )
    (comp (ref "R54")
      (value "4.7k")
      (fields
        (field (name "BOM_Manufacturer Part") "0805W8F4701T5E")
        (field (name "BOM_Supplier Part") "C17673")
      )
      (libsource (lib "") (part "R_0805_US"))
    )
    (comp (ref "R55")
      (value "10K")
      (fields
        (field (name "BOM_Manufacturer Part") "RK10J12E002L")
        (field (name "BOM_Supplier Part") "C231765")
      )
      (libsource (lib "") (part "RK10J12E002L"))
    )
    (comp (ref "R56")
      (value "100")
      (fields
        (field (name "BOM_Manufacturer Part") "CR0805F81000G")
        (field (name "BOM_Supplier Part") "C101403")
      )
      (libsource (lib "") (part "R_0805_US"))
    )
    (comp (ref "R57")
      (value "100")
      (fields
        (field (name "BOM_Manufacturer Part") "CR0805F81000G")
        (field (name "BOM_Supplier Part") "C101403")
      )
      (libsource (lib "") (part "R_0805_US"))
    )
    (comp (ref "R58")
      (value "1k")
      (fields
        (field (name "BOM_Manufacturer Part") "0805W8F1001T5E")
        (field (name "BOM_Supplier Part") "C17513")
      )
      (libsource (lib "") (part "Res_0805(1/8W)_US"))
    )
    (comp (ref "R59")
      (value "1k")
      (fields
        (field (name "BOM_Manufacturer Part") "0805W8F1001T5E")
        (field (name "BOM_Supplier Part") "C17513")
      )
      (libsource (lib "") (part "Res_0805(1/8W)_US"))
    )
    (comp (ref "R60")
      (value "1K")
      (fields
        (field (name "BOM_Manufacturer Part") "RS-05K3301FT")
        (field (name "BOM_Supplier Part") "C294703")
      )
      (libsource (lib "") (part "Res_0805(1/8W)_US_2"))
    )
    (comp (ref "R61")
      (value "470")
      (fields
        (field (name "BOM_Manufacturer Part") "RC0805FR-07470RL")
        (field (name "BOM_Supplier Part") "C114564")
      )
      (libsource (lib "") (part "R_0805_US_2"))
    )
    (comp (ref "R62")
      (value "470")
      (fields
        (field (name "BOM_Manufacturer Part") "RC0805FR-07470RL")
        (field (name "BOM_Supplier Part") "C114564")
      )
      (libsource (lib "") (part "R_0805_US_2"))
    )
    (comp (ref "R63")
      (value "47k")
      (fields
        (field (name "BOM_Manufacturer Part") "RS-05K4702FT")
        (field (name "BOM_Supplier Part") "C136580")
      )
      (libsource (lib "") (part "R_0805_US"))
    )
    (comp (ref "R64")
      (value "20k")
      (fields
        (field (name "BOM_Manufacturer Part") "RS-05K2002FT")
        (field (name "BOM_Supplier Part") "C136576")
      )
      (libsource (lib "") (part "R_0805_US_3"))
    )
    (comp (ref "R65")
      (value "4.7k")
      (fields
        (field (name "BOM_Manufacturer Part") "0805W8F4701T5E")
        (field (name "BOM_Supplier Part") "C17673")
      )
      (libsource (lib "") (part "R_0805_US"))
    )
    (comp (ref "R66")
      (value "4.7k")
      (fields
        (field (name "BOM_Manufacturer Part") "0805W8F4701T5E")
        (field (name "BOM_Supplier Part") "C17673")
      )
      (libsource (lib "") (part "R_0805_US"))
    )
    (comp (ref "R67")
      (value "4.7k")
      (fields
        (field (name "BOM_Manufacturer Part") "0805W8F4701T5E")
        (field (name "BOM_Supplier Part") "C17673")
      )
      (libsource (lib "") (part "R_0805_US"))
    )
    (comp (ref "R68")
      (value "4.7k")
      (fields
        (field (name "BOM_Manufacturer Part") "0805W8F4701T5E")
        (field (name "BOM_Supplier Part") "C17673")
      )
      (libsource (lib "") (part "R_0805_US"))
    )
    (comp (ref "R69")
      (value "4.7k")
      (fields
        (field (name "BOM_Manufacturer Part") "0805W8F4701T5E")
        (field (name "BOM_Supplier Part") "C17673")
      )
      (libsource (lib "") (part "R_0805_US"))
    )
    (comp (ref "R70")
      (value "4.7k")
      (fields
        (field (name "BOM_Manufacturer Part") "0805W8F4701T5E")
        (field (name "BOM_Supplier Part") "C17673")
      )
      (libsource (lib "") (part "R_0805_US"))
    )
    (comp (ref "R71")
      (value "220")
      (fields
        (field (name "BOM_Manufacturer Part") "RC0805FR-07220RL")
        (field (name "BOM_Supplier Part") "C114519")
      )
      (libsource (lib "") (part "R_0805_US"))
    )
    (comp (ref "R72")
      (value "220")
      (fields
        (field (name "BOM_Manufacturer Part") "RC0805FR-07220RL")
        (field (name "BOM_Supplier Part") "C114519")
      )
      (libsource (lib "") (part "R_0805_US"))
    )
    (comp (ref "R73")
      (value "220")
      (fields
        (field (name "BOM_Manufacturer Part") "RC0805FR-07220RL")
        (field (name "BOM_Supplier Part") "C114519")
      )
      (libsource (lib "") (part "R_0805_US"))
    )
    (comp (ref "R74")
      (value "220")
      (fields
        (field (name "BOM_Manufacturer Part") "RC0805FR-07220RL")
        (field (name "BOM_Supplier Part") "C114519")
      )
      (libsource (lib "") (part "R_0805_US"))
    )
    (comp (ref "R75")
      (value "10k")
      (fields
        (field (name "BOM_Manufacturer Part") "RTT051002FTP")
        (field (name "BOM_Supplier Part") "C103904")
      )
      (libsource (lib "") (part "R_0805_US"))
    )
    (comp (ref "R76")
      (value "10k")
      (fields
        (field (name "BOM_Manufacturer Part") "RTT051002FTP")
        (field (name "BOM_Supplier Part") "C103904")
      )
      (libsource (lib "") (part "R_0805_US"))
    )
    (comp (ref "RIGHT1")
      (value "K2-1817UQ-C4SW-01")
      (fields (field (name "BOM_Supplier Part") "C128939"))
      (libsource (lib "") (part "K2-1817UQ-C4SW-01_3"))
    )
    (comp (ref "SELECT1")
      (value "K2-1817UQ-C4SW-01")
      (fields (field (name "BOM_Supplier Part") "C128939"))
      (libsource (lib "") (part "K2-1817UQ-C4SW-01_1"))
    )
    (comp (ref "SP2")
      (value "SPEAKER-FS-2308-P9.2")
      (fields (field (name "BOM_Supplier Part") "C482322"))
      (libsource (lib "") (part "SPEAKER-FS-2308-P9.2"))
    )
    (comp (ref "START1")
      (value "K2-1817UQ-C4SW-01")
      (fields (field (name "BOM_Supplier Part") "C128939"))
      (libsource (lib "") (part "K2-1817UQ-C4SW-01_2"))
    )
    (comp (ref "SW1")
      (value "MSK12C02")
      (fields (field (name "BOM_Supplier Part") "C431540"))
      (libsource (lib "") (part "MSK12C02"))
    )
    (comp (ref "U4")
      (value "TP4056")
      (fields (field (name "BOM_Supplier Part") "C725790"))
      (libsource (lib "") (part "TP4056_C725790"))
    )
    (comp (ref "U9")
      (value "MPU-6050_C24112")
      (fields (field (name "BOM_Manufacturer Part") "MPU-6050") (field (name "BOM_Supplier Part") "C24112"))
      (libsource (lib "") (part "MPU-6050_C24112"))
    )
    (comp (ref "U10")
      (value "AMS1117")
      (fields
        (field (name "BOM_Manufacturer Part") "AMS1117-3.3")
        (field (name "BOM_Supplier Part") "C369933")
      )
      (libsource (lib "") (part "AMS1117-3.3_C369933"))
    )
    (comp (ref "U11")
      (value "AZ431AN-ATRE1")
      (fields (field (name "BOM_Supplier Part") "C84138"))
      (libsource (lib "") (part "AZ431AN-ATRE1"))
    )
    (comp (ref "U12")
      (value "CH340C")
      (fields (field (name "BOM_Supplier Part") "C84681"))
      (libsource (lib "") (part "CH340C"))
    )
    (comp (ref "U13")
      (value "FM8002A")
      (fields (field (name "BOM_Supplier Part") "C94625"))
      (libsource (lib "") (part "FM8002A"))
    )
    (comp (ref "U14")
      (value "ESP32-WROOM-32DC")
      (fields (field (name "BOM_Supplier Part") "C473013"))
      (libsource (lib "") (part "ESP32-WROOM-32DC"))
    )
    (comp (ref "UP1")
      (value "K2-1817UQ-C4SW-01")
      (fields (field (name "BOM_Supplier Part") "C128939"))
      (libsource (lib "") (part "K2-1817UQ-C4SW-01_7"))
    )
    (comp (ref "USB1")
      (value "TYPE-C16PIN")
      (fields (field (name "BOM_Supplier Part") "C393939"))
      (libsource (lib "") (part "TYPE-C16PIN"))
    )
  )
  (nets
    (net (code "1") (name "4.2V") (class "Default")
      (node (ref "C31") (pin "2") (pinfunction "2_2") (pintype "unspecified"))
      (node (ref "C9") (pin "2") (pinfunction "2_2") (pintype "unspecified"))
      (node (ref "Q3") (pin "3") (pinfunction "C_3") (pintype "input"))
      (node (ref "Q4") (pin "3") (pinfunction "C_3") (pintype "input"))
      (node (ref "R28") (pin "1") (pinfunction "1_1") (pintype "unspecified"))
      (node (ref "R29") (pin "1") (pinfunction "1_1") (pintype "unspecified"))
      (node (ref "R47") (pin "1") (pinfunction "1_1") (pintype "unspecified"))
      (node (ref "R48") (pin "1") (pinfunction "1_1") (pintype "unspecified"))
      (node (ref "SW1") (pin "2") (pinfunction "2_2") (pintype "unspecified"))
      (node (ref "SW1") (pin "3") (pinfunction "3_3") (pintype "unspecified"))
      (node (ref "SW3") (pin "2") (pinfunction "2_2") (pintype "unspecified"))
      (node (ref "SW3") (pin "3") (pinfunction "3_3") (pintype "unspecified"))
      (node (ref "U4") (pin "5") (pinfunction "BAT_5") (pintype "unspecified"))
      (node (ref "U8") (pin "5") (pinfunction "BAT_5") (pintype "unspecified"))
    )
    (net (code "2") (name "DTR") (class "Default")
      (node (ref "Q2") (pin "1") (pinfunction "E_1") (pintype "input"))
      (node (ref "Q5") (pin "1") (pinfunction "E_1") (pintype "input"))
      (node (ref "R1") (pin "1") (pinfunction "1_1") (pintype "unspecified"))
      (node (ref "R76") (pin "1") (pinfunction "1_1") (pintype "unspecified"))
      (node (ref "U12") (pin "13") (pinfunction "DTR#_13") (pintype "unspecified"))
      (node (ref "U5") (pin "13") (pinfunction "DTR#_13") (pintype "unspecified"))
    )
    (net (code "3") (name "EN") (class "Default")
      (node (ref "C17") (pin "2") (pinfunction "2_2") (pintype "unspecified"))
      (node (ref "C50") (pin "2") (pinfunction "2_2") (pintype "unspecified"))
      (node (ref "Q1") (pin "3") (pinfunction "C_3") (pintype "input"))
      (node (ref "Q6") (pin "3") (pinfunction "C_3") (pintype "input"))
      (node (ref "R15") (pin "2") (pinfunction "2_2") (pintype "unspecified"))
      (node (ref "R25") (pin "2") (pinfunction "2_2") (pintype "unspecified"))
      (node (ref "R52") (pin "2") (pinfunction "2_2") (pintype "unspecified"))
      (node (ref "R62") (pin "2") (pinfunction "2_2") (pintype "unspecified"))
      (node (ref "U1") (pin "3") (pinfunction "EN_3") (pintype "unspecified"))
      (node (ref "U14") (pin "3") (pinfunction "EN_3") (pintype "unspecified"))
    )
    (net (code "4") (name "GND") (class "Default")
      (node (ref "BOOT") (pin "1") (pinfunction "1_1") (pintype "unspecified"))
      (node (ref "BOOT") (pin "2") (pinfunction "2_2") (pintype "unspecified"))
      (node (ref "BOOT") (pin "4") (pinfunction "4_4") (pintype "unspecified"))
      (node (ref "BOOT1") (pin "1") (pinfunction "1_1") (pintype "unspecified"))
      (node (ref "BOOT1") (pin "2") (pinfunction "2_2") (pintype "unspecified"))
      (node (ref "BOOT1") (pin "4") (pinfunction "4_4") (pintype "unspecified"))
      (node (ref "C1") (pin "1") (pinfunction "1_1") (pintype "unspecified"))
      (node (ref "C10") (pin "2") (pinfunction "2_2") (pintype "unspecified"))
      (node (ref "C11") (pin "1") (pinfunction "1_1") (pintype "unspecified"))
      (node (ref "C12") (pin "1") (pinfunction "1_1") (pintype "unspecified"))
      (node (ref "C13") (pin "1") (pinfunction "1_1") (pintype "unspecified"))
      (node (ref "C14") (pin "1") (pinfunction "1_1") (pintype "unspecified"))
      (node (ref "C15") (pin "2") (pinfunction "2_2") (pintype "unspecified"))
      (node (ref "C16") (pin "1") (pinfunction "1_1") (pintype "unspecified"))
      (node (ref "C17") (pin "1") (pinfunction "1_1") (pintype "unspecified"))
      (node (ref "C18") (pin "1") (pinfunction "1_1") (pintype "unspecified"))
      (node (ref "C19") (pin "2") (pinfunction "2_2") (pintype "unspecified"))
      (node (ref "C20") (pin "1") (pinfunction "1_1") (pintype "unspecified"))
      (node (ref "C21") (pin "1") (pinfunction "1_1") (pintype "unspecified"))
      (node (ref "C22") (pin "1") (pinfunction "1_1") (pintype "unspecified"))
      (node (ref "C23") (pin "1") (pinfunction "1_1") (pintype "unspecified"))
      (node (ref "C24") (pin "1") (pinfunction "1_1") (pintype "unspecified"))
      (node (ref "C25") (pin "2") (pinfunction "2_2") (pintype "unspecified"))
      (node (ref "C26") (pin "1") (pinfunction "1_1") (pintype "unspecified"))
      (node (ref "C27") (pin "1") (pinfunction "1_1") (pintype "unspecified"))
      (node (ref "C28") (pin "1") (pinfunction "1_1") (pintype "unspecified"))
      (node (ref "C29") (pin "1") (pinfunction "1_1") (pintype "unspecified"))
      (node (ref "C3") (pin "1") (pinfunction "1_1") (pintype "unspecified"))
      (node (ref "C30") (pin "1") (pinfunction "1_1") (pintype "unspecified"))
      (node (ref "C31") (pin "1") (pinfunction "1_1") (pintype "unspecified"))
      (node (ref "C32") (pin "1") (pinfunction "1_1") (pintype "unspecified"))
      (node (ref "C33") (pin "1") (pinfunction "1_1") (pintype "unspecified"))
      (node (ref "C34") (pin "1") (pinfunction "1_1") (pintype "unspecified"))
      (node (ref "C35") (pin "1") (pinfunction "1_1") (pintype "unspecified"))
      (node (ref "C36") (pin "1") (pinfunction "1_1") (pintype "unspecified"))
      (node (ref "C37") (pin "2") (pinfunction "2_2") (pintype "unspecified"))
      (node (ref "C38") (pin "1") (pinfunction "1_1") (pintype "unspecified"))
      (node (ref "C39") (pin "1") (pinfunction "1_1") (pintype "unspecified"))
      (node (ref "C4") (pin "2") (pinfunction "2_2") (pintype "unspecified"))
      (node (ref "C40") (pin "1") (pinfunction "1_1") (pintype "unspecified"))
      (node (ref "C41") (pin "1") (pinfunction "1_1") (pintype "unspecified"))
      (node (ref "C42") (pin "1") (pinfunction "1_1") (pintype "unspecified"))
      (node (ref "C43") (pin "2") (pinfunction "2_2") (pintype "unspecified"))
      (node (ref "C44") (pin "1") (pinfunction "1_1") (pintype "unspecified"))
      (node (ref "C45") (pin "1") (pinfunction "1_1") (pintype "unspecified"))
      (node (ref "C46") (pin "2") (pinfunction "2_2") (pintype "unspecified"))
      (node (ref "C47") (pin "2") (pinfunction "2_2") (pintype "unspecified"))
      (node (ref "C48") (pin "2") (pinfunction "2_2") (pintype "unspecified"))
      (node (ref "C49") (pin "2") (pinfunction "2_2") (pintype "unspecified"))
      (node (ref "C5") (pin "2") (pinfunction "2_2") (pintype "unspecified"))
      (node (ref "C50") (pin "1") (pinfunction "1_1") (pintype "unspecified"))
      (node (ref "C51") (pin "1") (pinfunction "1_1") (pintype "unspecified"))
      (node (ref "C52") (pin "1") (pinfunction "1_1") (pintype "unspecified"))
      (node (ref "C53") (pin "1") (pinfunction "1_1") (pintype "unspecified"))
      (node (ref "C54") (pin "1") (pinfunction "1_1") (pintype "unspecified"))
      (node (ref "C55") (pin "1") (pinfunction "1_1") (pintype "unspecified"))
      (node (ref "C56") (pin "1") (pinfunction "1_1") (pintype "unspecified"))
      (node (ref "C57") (pin "2") (pinfunction "2_2") (pintype "unspecified"))
      (node (ref "C58") (pin "1") (pinfunction "1_1") (pintype "unspecified"))
      (node (ref "C6") (pin "2") (pinfunction "2_2") (pintype "unspecified"))
      (node (ref "C60") (pin "1") (pinfunction "1_1") (pintype "unspecified"))
      (node (ref "C7") (pin "1") (pinfunction "1_1") (pintype "unspecified"))
      (node (ref "C8") (pin "1") (pinfunction "1_1") (pintype "unspecified"))
      (node (ref "C9") (pin "1") (pinfunction "1_1") (pintype "unspecified"))
      (node (ref "DOWN") (pin "1") (pinfunction "1_1") (pintype "input"))
      (node (ref "DOWN1") (pin "1") (pinfunction "1_1") (pintype "input"))
      (node (ref "EN") (pin "1") (pinfunction "1_1") (pintype "unspecified"))
      (node (ref "EN") (pin "2") (pinfunction "2_2") (pintype "unspecified"))
      (node (ref "EN") (pin "4") (pinfunction "4_4") (pintype "unspecified"))
      (node (ref "EN1") (pin "1") (pinfunction "1_1") (pintype "unspecified"))
      (node (ref "EN1") (pin "2") (pinfunction "2_2") (pintype "unspecified"))
      (node (ref "EN1") (pin "4") (pinfunction "4_4") (pintype "unspecified"))
      (node (ref "KEY-A") (pin "1") (pinfunction "1_1") (pintype "input"))
      (node (ref "KEY-A1") (pin "1") (pinfunction "1_1") (pintype "input"))
      (node (ref "KEY-B") (pin "1") (pinfunction "1_1") (pintype "input"))
      (node (ref "KEY-B1") (pin "1") (pinfunction "1_1") (pintype "input"))
      (node (ref "KEY-C") (pin "1") (pinfunction "1_1") (pintype "input"))
      (node (ref "KEY-C1") (pin "1") (pinfunction "1_1") (pintype "input"))
      (node (ref "KEY-D") (pin "1") (pinfunction "1_1") (pintype "input"))
      (node (ref "KEY-D1") (pin "1") (pinfunction "1_1") (pintype "input"))
      (node (ref "LB") (pin "2") (pinfunction "2_2") (pintype "unspecified"))
      (node (ref "LB1") (pin "2") (pinfunction "2_2") (pintype "unspecified"))
      (node (ref "LCD") (pin "1") (pinfunction "GND_1") (pintype "unspecified"))
      (node (ref "LCD") (pin "8") (pinfunction "GND_8") (pintype "unspecified"))
      (node (ref "LCD1") (pin "1") (pinfunction "GND_1") (pintype "unspecified"))
      (node (ref "LCD1") (pin "8") (pinfunction "GND_8") (pintype "unspecified"))
      (node (ref "LEFT") (pin "1") (pinfunction "1_1") (pintype "input"))
      (node (ref "LEFT1") (pin "1") (pinfunction "1_1") (pintype "input"))
      (node (ref "POWER") (pin "2") (pinfunction "2_2") (pintype "unspecified"))
      (node (ref "POWER1") (pin "2") (pinfunction "2_2") (pintype "unspecified"))
      (node (ref "R19") (pin "2") (pinfunction "2_2") (pintype "unspecified"))
      (node (ref "R22") (pin "1") (pinfunction "1_1") (pintype "unspecified"))
      (node (ref "R27") (pin "1") (pinfunction "1_1") (pintype "unspecified"))
      (node (ref "R3") (pin "1") (pinfunction "1_1") (pintype "unspecified"))
      (node (ref "R30") (pin "2") (pinfunction "2_2") (pintype "unspecified"))
      (node (ref "R32") (pin "1") (pinfunction "1_1") (pintype "unspecified"))
      (node (ref "R33") (pin "1") (pinfunction "1_1") (pintype "unspecified"))
      (node (ref "R4") (pin "1") (pinfunction "1_1") (pintype "unspecified"))
      (node (ref "R44") (pin "1") (pinfunction "1_1") (pintype "unspecified"))
      (node (ref "R45") (pin "1") (pinfunction "1_1") (pintype "unspecified"))
      (node (ref "R46") (pin "2") (pinfunction "2_2") (pintype "unspecified"))
      (node (ref "R5") (pin "1") (pinfunction "1_1") (pintype "unspecified"))
      (node (ref "R50") (pin "1") (pinfunction "1_1") (pintype "unspecified"))
      (node (ref "R55") (pin "1") (pinfunction "1_1") (pintype "unspecified"))
      (node (ref "R6") (pin "1") (pinfunction "1_1") (pintype "unspecified"))
      (node (ref "R60") (pin "2") (pinfunction "2_2") (pintype "unspecified"))
      (node (ref "R71") (pin "1") (pinfunction "1_1") (pintype "unspecified"))
      (node (ref "R72") (pin "1") (pinfunction "1_1") (pintype "unspecified"))
      (node (ref "R73") (pin "1") (pinfunction "1_1") (pintype "unspecified"))
      (node (ref "R74") (pin "1") (pinfunction "1_1") (pintype "unspecified"))
      (node (ref "RIGHT") (pin "1") (pinfunction "1_1") (pintype "input"))
      (node (ref "RIGHT1") (pin "1") (pinfunction "1_1") (pintype "input"))
      (node (ref "SELECT") (pin "1") (pinfunction "1_1") (pintype "input"))
      (node (ref "SELECT1") (pin "1") (pinfunction "1_1") (pintype "input"))
      (node (ref "START") (pin "1") (pinfunction "1_1") (pintype "input"))
      (node (ref "START1") (pin "1") (pinfunction "1_1") (pintype "input"))
      (node (ref "SW1") (pin "4") (pinfunction "4_4") (pintype "unspecified"))
      (node (ref "SW3") (pin "4") (pinfunction "4_4") (pintype "unspecified"))
      (node (ref "U1") (pin "1") (pinfunction "GND_1") (pintype "unspecified"))
      (node (ref "U1") (pin "15") (pinfunction "GND_15") (pintype "unspecified"))
      (node (ref "U1") (pin "38") (pinfunction "GND_38") (pintype "unspecified"))
      (node (ref "U1") (pin "39") (pinfunction "GND_39") (pintype "unspecified"))
      (node (ref "U10") (pin "1") (pinfunction "GND/ADJ_1") (pintype "unspecified"))
      (node (ref "U11") (pin "3") (pinfunction "A_3") (pintype "unspecified"))
      (node (ref "U12") (pin "1") (pinfunction "GND_1") (pintype "unspecified"))
      (node (ref "U13") (pin "1") (pinfunction "SHUTDOWN_1") (pintype "unspecified"))
      (node (ref "U13") (pin "7") (pinfunction "GND_7") (pintype "unspecified"))
      (node (ref "U14") (pin "1") (pinfunction "GND_1") (pintype "unspecified"))
      (node (ref "U14") (pin "15") (pinfunction "GND_15") (pintype "unspecified"))
      (node (ref "U14") (pin "38") (pinfunction "GND_38") (pintype "unspecified"))
      (node (ref "U14") (pin "39") (pinfunction "GND_39") (pintype "unspecified"))
      (node (ref "U2") (pin "1") (pinfunction "SHUTDOWN_1") (pintype "unspecified"))
      (node (ref "U2") (pin "7") (pinfunction "GND_7") (pintype "unspecified"))
      (node (ref "U3") (pin "1") (pinfunction "GND/ADJ_1") (pintype "unspecified"))
      (node (ref "U4") (pin "1") (pinfunction "TEMP_1") (pintype "unspecified"))
      (node (ref "U4") (pin "3") (pinfunction "GND_3") (pintype "unspecified"))
      (node (ref "U4") (pin "9") (pinfunction "EP_9") (pintype "unspecified"))
      (node (ref "U5") (pin "1") (pinfunction "GND_1") (pintype "unspecified"))
      (node (ref "U6") (pin "1") (pinfunction "CLKIN_1") (pintype "unspecified"))
      (node (ref "U6") (pin "11") (pinfunction "FSYNC_11") (pintype "unspecified"))
      (node (ref "U6") (pin "14") (pinfunction "NC_14") (pintype "unspecified"))
      (node (ref "U6") (pin "15") (pinfunction "NC_15") (pintype "unspecified"))
      (node (ref "U6") (pin "16") (pinfunction "NC_16") (pintype "unspecified"))
      (node (ref "U6") (pin "17") (pinfunction "NC_17") (pintype "unspecified"))
      (node (ref "U6") (pin "18") (pinfunction "GND_18") (pintype "unspecified"))
      (node (ref "U6") (pin "2") (pinfunction "NC_2") (pintype "unspecified"))
      (node (ref "U6") (pin "25") (pinfunction "EP_25") (pintype "unspecified"))
      (node (ref "U6") (pin "3") (pinfunction "NC_3") (pintype "unspecified"))
      (node (ref "U6") (pin "4") (pinfunction "NC_4") (pintype "unspecified"))
      (node (ref "U6") (pin "5") (pinfunction "NC_5") (pintype "unspecified"))
      (node (ref "U6") (pin "9") (pinfunction "AD0_9") (pintype "unspecified"))
      (node (ref "U7") (pin "3") (pinfunction "A_3") (pintype "unspecified"))
      (node (ref "U8") (pin "9") (pinfunction "EP_9") (pintype "unspecified"))
      (node (ref "U9") (pin "1") (pinfunction "CLKIN_1") (pintype "unspecified"))
      (node (ref "U9") (pin "11") (pinfunction "FSYNC_11") (pintype "unspecified"))
      (node (ref "U9") (pin "14") (pinfunction "NC_14") (pintype "unspecified"))
      (node (ref "U9") (pin "15") (pinfunction "NC_15") (pintype "unspecified"))
      (node (ref "U9") (pin "16") (pinfunction "NC_16") (pintype "unspecified"))
      (node (ref "U9") (pin "17") (pinfunction "NC_17") (pintype "unspecified"))
      (node (ref "U9") (pin "18") (pinfunction "GND_18") (pintype "unspecified"))
      (node (ref "U9") (pin "2") (pinfunction "NC_2") (pintype "unspecified"))
      (node (ref "U9") (pin "25") (pinfunction "EP_25") (pintype "unspecified"))
      (node (ref "U9") (pin "3") (pinfunction "NC_3") (pintype "unspecified"))
      (node (ref "U9") (pin "4") (pinfunction "NC_4") (pintype "unspecified"))
      (node (ref "U9") (pin "5") (pinfunction "NC_5") (pintype "unspecified"))
      (node (ref "U9") (pin "9") (pinfunction "AD0_9") (pintype "unspecified"))
      (node (ref "UP") (pin "1") (pinfunction "1_1") (pintype "input"))
      (node (ref "UP1") (pin "1") (pinfunction "1_1") (pintype "input"))
      (node (ref "USB1") (pin "1") (pinfunction "SHELL_1") (pintype "unspecified"))
      (node (ref "USB1") (pin "2") (pinfunction "SHELL_2") (pintype "unspecified"))
      (node (ref "USB1") (pin "3") (pinfunction "SHELL_3") (pintype "unspecified"))
      (node (ref "USB1") (pin "4") (pinfunction "SHELL_4") (pintype "unspecified"))
      (node (ref "USB1") (pin "A1B12") (pinfunction "GND_A1B12") (pintype "unspecified"))
      (node (ref "USB1") (pin "B1A12") (pinfunction "GND_B1A12") (pintype "unspecified"))
      (node (ref "USB2") (pin "1") (pinfunction "SHELL_1") (pintype "unspecified"))
      (node (ref "USB2") (pin "2") (pinfunction "SHELL_2") (pintype "unspecified"))
      (node (ref "USB2") (pin "3") (pinfunction "SHELL_3") (pintype "unspecified"))
      (node (ref "USB2") (pin "4") (pinfunction "SHELL_4") (pintype "unspecified"))
      (node (ref "USB2") (pin "A1B12") (pinfunction "GND_A1B12") (pintype "unspecified"))
      (node (ref "USB2") (pin "B1A12") (pinfunction "GND_B1A12") (pintype "unspecified"))
    )
    (net (code "5") (name "GPIO0") (class "Default")
      (node (ref "Q2") (pin "3") (pinfunction "C_3") (pintype "input"))
      (node (ref "Q5") (pin "3") (pinfunction "C_3") (pintype "input"))
      (node (ref "R16") (pin "2") (pinfunction "2_2") (pintype "unspecified"))
      (node (ref "R26") (pin "2") (pinfunction "2_2") (pintype "unspecified"))
      (node (ref "R51") (pin "2") (pinfunction "2_2") (pintype "unspecified"))
      (node (ref "R61") (pin "2") (pinfunction "2_2") (pintype "unspecified"))
      (node (ref "U1") (pin "25") (pinfunction "IO0_25") (pintype "unspecified"))
      (node (ref "U14") (pin "25") (pinfunction "IO0_25") (pintype "unspecified"))
    )
    (net (code "6") (name "GPIO2") (class "Default")
      (node (ref "R27") (pin "2") (pinfunction "2_2") (pintype "unspecified"))
      (node (ref "R50") (pin "2") (pinfunction "2_2") (pintype "unspecified"))
      (node (ref "U1") (pin "24") (pinfunction "IO2_24") (pintype "unspecified"))
      (node (ref "U14") (pin "24") (pinfunction "IO2_24") (pintype "unspecified"))
    )
    (net (code "7") (name "GPIO12_Key-D") (class "Default")
      (node (ref "C30") (pin "2") (pinfunction "2_2") (pintype "unspecified"))
      (node (ref "KEY-D") (pin "2") (pinfunction "2_2") (pintype "input"))
      (node (ref "R36") (pin "2") (pinfunction "2_2") (pintype "unspecified"))
      (node (ref "U1") (pin "14") (pinfunction "IO12_14") (pintype "unspecified"))
    )
    (net (code "8") (name "GPIO13_Key-Select") (class "Default")
      (node (ref "C21") (pin "2") (pinfunction "2_2") (pintype "unspecified"))
      (node (ref "C41") (pin "2") (pinfunction "2_2") (pintype "unspecified"))
      (node (ref "R11") (pin "2") (pinfunction "2_2") (pintype "unspecified"))
      (node (ref "R66") (pin "2") (pinfunction "2_2") (pintype "unspecified"))
      (node (ref "SELECT") (pin "2") (pinfunction "2_2") (pintype "input"))
      (node (ref "SELECT1") (pin "2") (pinfunction "2_2") (pintype "input"))
      (node (ref "U1") (pin "16") (pinfunction "IO13_16") (pintype "unspecified"))
      (node (ref "U14") (pin "16") (pinfunction "IO13_16") (pintype "unspecified"))
    )
    (net (code "9") (name "GPIO14_Key-Up") (class "Default")
      (node (ref "C18") (pin "2") (pinfunction "2_2") (pintype "unspecified"))
      (node (ref "C44") (pin "2") (pinfunction "2_2") (pintype "unspecified"))
      (node (ref "R7") (pin "2") (pinfunction "2_2") (pintype "unspecified"))
      (node (ref "R70") (pin "2") (pinfunction "2_2") (pintype "unspecified"))
      (node (ref "U1") (pin "13") (pinfunction "IO14_13") (pintype "unspecified"))
      (node (ref "U14") (pin "13") (pinfunction "IO14_13") (pintype "unspecified"))
      (node (ref "UP") (pin "2") (pinfunction "2_2") (pintype "input"))
      (node (ref "UP1") (pin "2") (pinfunction "2_2") (pintype "input"))
    )
    (net (code "10") (name "GPIO16_Key-Start") (class "Default")
      (node (ref "C22") (pin "2") (pinfunction "2_2") (pintype "unspecified"))
      (node (ref "C40") (pin "2") (pinfunction "2_2") (pintype "unspecified"))
      (node (ref "R12") (pin "2") (pinfunction "2_2") (pintype "unspecified"))
      (node (ref "R65") (pin "2") (pinfunction "2_2") (pintype "unspecified"))
      (node (ref "START") (pin "2") (pinfunction "2_2") (pintype "input"))
      (node (ref "START1") (pin "2") (pinfunction "2_2") (pintype "input"))
      (node (ref "U1") (pin "27") (pinfunction "IO16_27") (pintype "unspecified"))
      (node (ref "U14") (pin "27") (pinfunction "IO16_27") (pintype "unspecified"))
    )
    (net (code "11") (name "GPIO19_Key-D") (class "Default")
      (node (ref "C32") (pin "2") (pinfunction "2_2") (pintype "unspecified"))
      (node (ref "KEY-D1") (pin "2") (pinfunction "2_2") (pintype "input"))
      (node (ref "R41") (pin "2") (pinfunction "2_2") (pintype "unspecified"))
      (node (ref "U14") (pin "31") (pinfunction "IO19_31") (pintype "unspecified"))
    )
    (net (code "12") (name "GPIO25_Audio") (class "Default")
      (node (ref "JP1") (pin "1") (pinfunction "1_1") (pintype "unspecified"))
      (node (ref "JP2") (pin "1") (pinfunction "1_1") (pintype "unspecified"))
      (node (ref "R22") (pin "5") (pinfunction "5_5") (pintype "unspecified"))
      (node (ref "R55") (pin "5") (pinfunction "5_5") (pintype "unspecified"))
      (node (ref "U1") (pin "10") (pinfunction "IO25_10") (pintype "unspecified"))
      (node (ref "U14") (pin "10") (pinfunction "IO25_10") (pintype "unspecified"))
    )
    (net (code "13") (name "GPIO26_Key-C") (class "Default")
      (node (ref "C29") (pin "2") (pinfunction "2_2") (pintype "unspecified"))
      (node (ref "C33") (pin "2") (pinfunction "2_2") (pintype "unspecified"))
      (node (ref "KEY-C") (pin "2") (pinfunction "2_2") (pintype "input"))
      (node (ref "KEY-C1") (pin "2") (pinfunction "2_2") (pintype "input"))
      (node (ref "R35") (pin "2") (pinfunction "2_2") (pintype "unspecified"))
      (node (ref "R42") (pin "2") (pinfunction "2_2") (pintype "unspecified"))
      (node (ref "U1") (pin "11") (pinfunction "IO26_11") (pintype "unspecified"))
      (node (ref "U14") (pin "11") (pinfunction "IO26_11") (pintype "unspecified"))
    )
    (net (code "14") (name "GPIO27_Key-Left") (class "Default")
      (node (ref "C19") (pin "1") (pinfunction "1_1") (pintype "unspecified"))
      (node (ref "C43") (pin "1") (pinfunction "1_1") (pintype "unspecified"))
      (node (ref "LEFT") (pin "2") (pinfunction "2_2") (pintype "input"))
      (node (ref "LEFT1") (pin "2") (pinfunction "2_2") (pintype "input"))
      (node (ref "R68") (pin "2") (pinfunction "2_2") (pintype "unspecified"))
      (node (ref "R9") (pin "2") (pinfunction "2_2") (pintype "unspecified"))
      (node (ref "U1") (pin "12") (pinfunction "IO27_12") (pintype "unspecified"))
      (node (ref "U14") (pin "12") (pinfunction "IO27_12") (pintype "unspecified"))
    )
    (net (code "15") (name "GPIO32_Key-Down") (class "Default")
      (node (ref "C16") (pin "2") (pinfunction "2_2") (pintype "unspecified"))
      (node (ref "C45") (pin "2") (pinfunction "2_2") (pintype "unspecified"))
      (node (ref "DOWN") (pin "2") (pinfunction "2_2") (pintype "input"))
      (node (ref "DOWN1") (pin "2") (pinfunction "2_2") (pintype "input"))
      (node (ref "R69") (pin "2") (pinfunction "2_2") (pintype "unspecified"))
      (node (ref "R8") (pin "2") (pinfunction "2_2") (pintype "unspecified"))
      (node (ref "U1") (pin "8") (pinfunction "IO32_8") (pintype "unspecified"))
      (node (ref "U14") (pin "8") (pinfunction "IO32_8") (pintype "unspecified"))
    )
    (net (code "16") (name "GPIO33_Key-Right") (class "Default")
      (node (ref "C20") (pin "2") (pinfunction "2_2") (pintype "unspecified"))
      (node (ref "C42") (pin "2") (pinfunction "2_2") (pintype "unspecified"))
      (node (ref "R10") (pin "2") (pinfunction "2_2") (pintype "unspecified"))
      (node (ref "R67") (pin "2") (pinfunction "2_2") (pintype "unspecified"))
      (node (ref "RIGHT") (pin "2") (pinfunction "2_2") (pintype "input"))
      (node (ref "RIGHT1") (pin "2") (pinfunction "2_2") (pintype "input"))
      (node (ref "U1") (pin "9") (pinfunction "IO33_9") (pintype "unspecified"))
      (node (ref "U14") (pin "9") (pinfunction "IO33_9") (pintype "unspecified"))
    )
    (net (code "17") (name "GPIO34_Key-B") (class "Default")
      (node (ref "C24") (pin "2") (pinfunction "2_2") (pintype "unspecified"))
      (node (ref "C38") (pin "2") (pinfunction "2_2") (pintype "unspecified"))
      (node (ref "KEY-B") (pin "2") (pinfunction "2_2") (pintype "input"))
      (node (ref "KEY-B1") (pin "2") (pinfunction "2_2") (pintype "input"))
      (node (ref "R24") (pin "2") (pinfunction "2_2") (pintype "unspecified"))
      (node (ref "R53") (pin "2") (pinfunction "2_2") (pintype "unspecified"))
      (node (ref "U1") (pin "6") (pinfunction "IO34_6") (pintype "unspecified"))
      (node (ref "U14") (pin "6") (pinfunction "IO34_6") (pintype "unspecified"))
    )
    (net (code "18") (name "GPIO35_Key-A") (class "Default")
      (node (ref "C23") (pin "2") (pinfunction "2_2") (pintype "unspecified"))
      (node (ref "C39") (pin "2") (pinfunction "2_2") (pintype "unspecified"))
      (node (ref "KEY-A") (pin "2") (pinfunction "2_2") (pintype "input"))
      (node (ref "KEY-A1") (pin "2") (pinfunction "2_2") (pintype "input"))
      (node (ref "R23") (pin "2") (pinfunction "2_2") (pintype "unspecified"))
      (node (ref "R54") (pin "2") (pinfunction "2_2") (pintype "unspecified"))
      (node (ref "U1") (pin "7") (pinfunction "IO35_7") (pintype "unspecified"))
      (node (ref "U14") (pin "7") (pinfunction "IO35_7") (pintype "unspecified"))
    )
    (net (code "19") (name "LCD-CS") (class "Default")
      (node (ref "LCD") (pin "5") (pinfunction "CS_5") (pintype "unspecified"))
      (node (ref "LCD1") (pin "5") (pinfunction "CS_5") (pintype "unspecified"))
      (node (ref "U1") (pin "29") (pinfunction "IO5_29") (pintype "unspecified"))
      (node (ref "U14") (pin "29") (pinfunction "IO5_29") (pintype "unspecified"))
    )
    (net (code "20") (name "LCD-DC") (class "Default")
      (node (ref "LCD") (pin "4") (pinfunction "DC_4") (pintype "unspecified"))
      (node (ref "LCD1") (pin "4") (pinfunction "DC_4") (pintype "unspecified"))
      (node (ref "U1") (pin "28") (pinfunction "IO17_28") (pintype "unspecified"))
      (node (ref "U14") (pin "28") (pinfunction "IO17_28") (pintype "unspecified"))
    )
    (net (code "21") (name "LCD-MOSI") (class "Default")
      (node (ref "LCD") (pin "6") (pinfunction "SDA_6") (pintype "unspecified"))
      (node (ref "LCD1") (pin "6") (pinfunction "SDA_6") (pintype "unspecified"))
      (node (ref "U1") (pin "37") (pinfunction "IO23_37") (pintype "unspecified"))
      (node (ref "U14") (pin "37") (pinfunction "IO23_37") (pintype "unspecified"))
    )
    (net (code "22") (name "LCD-RST") (class "Default")
      (node (ref "LCD") (pin "2") (pinfunction "RST_2") (pintype "unspecified"))
      (node (ref "LCD1") (pin "2") (pinfunction "RST_2") (pintype "unspecified"))
      (node (ref "U1") (pin "26") (pinfunction "IO4_26") (pintype "unspecified"))
      (node (ref "U14") (pin "26") (pinfunction "IO4_26") (pintype "unspecified"))
    )
    (net (code "23") (name "LCD-SCLK") (class "Default")
      (node (ref "LCD") (pin "3") (pinfunction "SCL_3") (pintype "unspecified"))
      (node (ref "LCD1") (pin "3") (pinfunction "SCL_3") (pintype "unspecified"))
      (node (ref "U1") (pin "30") (pinfunction "IO18_30") (pintype "unspecified"))
      (node (ref "U14") (pin "30") (pinfunction "IO18_30") (pintype "unspecified"))
    )
    (net (code "24") (name "LED-K1") (class "Default")
      (node (ref "LCD") (pin "11") (pinfunction "LED-K1_11") (pintype "unspecified"))
      (node (ref "LCD1") (pin "11") (pinfunction "LED-K1_11") (pintype "unspecified"))
      (node (ref "R3") (pin "2") (pinfunction "2_2") (pintype "unspecified"))
      (node (ref "R74") (pin "2") (pinfunction "2_2") (pintype "unspecified"))
    )
    (net (code "25") (name "LED-K2") (class "Default")
      (node (ref "LCD") (pin "12") (pinfunction "LED-K2_12") (pintype "unspecified"))
      (node (ref "LCD1") (pin "12") (pinfunction "LED-K2_12") (pintype "unspecified"))
      (node (ref "R4") (pin "2") (pinfunction "2_2") (pintype "unspecified"))
      (node (ref "R73") (pin "2") (pinfunction "2_2") (pintype "unspecified"))
    )
    (net (code "26") (name "LED-K3") (class "Default")
      (node (ref "LCD") (pin "13") (pinfunction "LED-K3_13") (pintype "unspecified"))
      (node (ref "LCD1") (pin "13") (pinfunction "LED-K3_13") (pintype "unspecified"))
      (node (ref "R5") (pin "2") (pinfunction "2_2") (pintype "unspecified"))
      (node (ref "R72") (pin "2") (pinfunction "2_2") (pintype "unspecified"))
    )
    (net (code "27") (name "LED-K4") (class "Default")
      (node (ref "LCD") (pin "14") (pinfunction "LED-K4_14") (pintype "unspecified"))
      (node (ref "LCD1") (pin "14") (pinfunction "LED-K4_14") (pintype "unspecified"))
      (node (ref "R6") (pin "2") (pinfunction "2_2") (pintype "unspecified"))
      (node (ref "R71") (pin "2") (pinfunction "2_2") (pintype "unspecified"))
    )
    (net (code "28") (name "Net-(BOOT-Pad3)") (class "Default")
      (node (ref "BOOT") (pin "3") (pinfunction "3_3") (pintype "unspecified"))
      (node (ref "R16") (pin "1") (pinfunction "1_1") (pintype "unspecified"))
    )
    (net (code "29") (name "Net-(BOOT1-Pad3)") (class "Default")
      (node (ref "BOOT1") (pin "3") (pinfunction "3_3") (pintype "unspecified"))
      (node (ref "R61") (pin "1") (pinfunction "1_1") (pintype "unspecified"))
    )
    (net (code "30") (name "Net-(C2-Pad1)") (class "Default")
      (node (ref "C2") (pin "1") (pinfunction "1_1") (pintype "unspecified"))
      (node (ref "JP1") (pin "2") (pinfunction "2_2") (pintype "unspecified"))
      (node (ref "R22") (pin "4") (pinfunction "4_4") (pintype "unspecified"))
    )
    (net (code "31") (name "Net-(C2-Pad2)") (class "Default")
      (node (ref "C2") (pin "2") (pinfunction "2_2") (pintype "unspecified"))
      (node (ref "R13") (pin "1") (pinfunction "1_1") (pintype "unspecified"))
    )
    (net (code "32") (name "Net-(C59-Pad1)") (class "Default")
      (node (ref "C59") (pin "1") (pinfunction "1_1") (pintype "unspecified"))
      (node (ref "JP2") (pin "2") (pinfunction "2_2") (pintype "unspecified"))
      (node (ref "R55") (pin "4") (pinfunction "4_4") (pintype "unspecified"))
    )
    (net (code "33") (name "Net-(C59-Pad2)") (class "Default")
      (node (ref "C59") (pin "2") (pinfunction "2_2") (pintype "unspecified"))
      (node (ref "R64") (pin "1") (pinfunction "1_1") (pintype "unspecified"))
    )
    (net (code "34") (name "Net-(CHG-A)") (class "Default")
      (node (ref "CHG") (pin "1") (pinfunction "A_1") (pintype "input"))
      (node (ref "R20") (pin "1") (pinfunction "1_1") (pintype "unspecified"))
    )
    (net (code "35") (name "Net-(CHG-C)") (class "Default")
      (node (ref "CHG") (pin "2") (pinfunction "C_2") (pintype "input"))
      (node (ref "U8") (pin "7") (pinfunction "CHRG_7") (pintype "unspecified"))
    )
    (net (code "36") (name "Net-(CHG1-A)") (class "Default")
      (node (ref "CHG1") (pin "1") (pinfunction "A_1") (pintype "input"))
      (node (ref "R59") (pin "1") (pinfunction "1_1") (pintype "unspecified"))
    )
    (net (code "37") (name "Net-(CHG1-C)") (class "Default")
      (node (ref "CHG1") (pin "2") (pinfunction "C_2") (pintype "input"))
      (node (ref "U4") (pin "7") (pinfunction "CHRG_7") (pintype "unspecified"))
    )
    (net (code "38") (name "Net-(EN-Pad3)") (class "Default")
      (node (ref "EN") (pin "3") (pinfunction "3_3") (pintype "unspecified"))
      (node (ref "R15") (pin "1") (pinfunction "1_1") (pintype "unspecified"))
    )
    (net (code "39") (name "Net-(EN1-Pad3)") (class "Default")
      (node (ref "EN1") (pin "3") (pinfunction "3_3") (pintype "unspecified"))
      (node (ref "R62") (pin "1") (pinfunction "1_1") (pintype "unspecified"))
    )
    (net (code "40") (name "Net-(F1-Pad2)") (class "Default")
      (node (ref "F1") (pin "2") (pinfunction "2_2") (pintype "unspecified"))
      (node (ref "USB2") (pin "A4B9") (pinfunction "VBUS_A4B9") (pintype "unspecified"))
      (node (ref "USB2") (pin "B4A9") (pinfunction "VBUS_B4A9") (pintype "unspecified"))
    )
    (net (code "41") (name "Net-(F2-Pad2)") (class "Default")
      (node (ref "F2") (pin "2") (pinfunction "2_2") (pintype "unspecified"))
      (node (ref "USB1") (pin "A4B9") (pinfunction "VBUS_A4B9") (pintype "unspecified"))
      (node (ref "USB1") (pin "B4A9") (pinfunction "VBUS_B4A9") (pintype "unspecified"))
    )
    (net (code "42") (name "Net-(FUL-A)") (class "Default")
      (node (ref "FUL") (pin "1") (pinfunction "A_1") (pintype "input"))
      (node (ref "R21") (pin "1") (pinfunction "1_1") (pintype "unspecified"))
    )
    (net (code "43") (name "Net-(FUL-C)") (class "Default")
      (node (ref "FUL") (pin "2") (pinfunction "C_2") (pintype "input"))
      (node (ref "U8") (pin "6") (pinfunction "STDBY_6") (pintype "unspecified"))
    )
    (net (code "44") (name "Net-(FUL1-A)") (class "Default")
      (node (ref "FUL1") (pin "1") (pinfunction "A_1") (pintype "input"))
      (node (ref "R58") (pin "1") (pinfunction "1_1") (pintype "unspecified"))
    )
    (net (code "45") (name "Net-(FUL1-C)") (class "Default")
      (node (ref "FUL1") (pin "2") (pinfunction "C_2") (pintype "input"))
      (node (ref "U4") (pin "6") (pinfunction "STDBY_6") (pintype "unspecified"))
    )
    (net (code "46") (name "Net-(LB-Pad1)") (class "Default")
      (node (ref "LB") (pin "1") (pinfunction "1_1") (pintype "unspecified"))
      (node (ref "R31") (pin "2") (pinfunction "2_2") (pintype "unspecified"))
    )
    (net (code "47") (name "Net-(LB1-Pad1)") (class "Default")
      (node (ref "LB1") (pin "1") (pinfunction "1_1") (pintype "unspecified"))
      (node (ref "R49") (pin "2") (pinfunction "2_2") (pintype "unspecified"))
    )
    (net (code "48") (name "Net-(POWER-Pad1)") (class "Default")
      (node (ref "POWER") (pin "1") (pinfunction "1_1") (pintype "unspecified"))
      (node (ref "R34") (pin "1") (pinfunction "1_1") (pintype "unspecified"))
    )
    (net (code "49") (name "Net-(POWER1-Pad1)") (class "Default")
      (node (ref "POWER1") (pin "1") (pinfunction "1_1") (pintype "unspecified"))
      (node (ref "R43") (pin "1") (pinfunction "1_1") (pintype "unspecified"))
    )
    (net (code "50") (name "Net-(Q1-B)") (class "Default")
      (node (ref "Q1") (pin "2") (pinfunction "B_2") (pintype "input"))
      (node (ref "R1") (pin "2") (pinfunction "2_2") (pintype "unspecified"))
    )
    (net (code "51") (name "Net-(Q2-B)") (class "Default")
      (node (ref "Q2") (pin "2") (pinfunction "B_2") (pintype "input"))
      (node (ref "R2") (pin "2") (pinfunction "2_2") (pintype "unspecified"))
    )
    (net (code "52") (name "Net-(Q3-B)") (class "Default")
      (node (ref "Q3") (pin "2") (pinfunction "B_2") (pintype "input"))
      (node (ref "R28") (pin "2") (pinfunction "2_2") (pintype "unspecified"))
      (node (ref "U7") (pin "2") (pinfunction "C_2") (pintype "unspecified"))
    )
    (net (code "53") (name "Net-(Q3-E)") (class "Default")
      (node (ref "Q3") (pin "1") (pinfunction "E_1") (pintype "input"))
      (node (ref "R31") (pin "1") (pinfunction "1_1") (pintype "unspecified"))
    )
    (net (code "54") (name "Net-(Q4-B)") (class "Default")
      (node (ref "Q4") (pin "2") (pinfunction "B_2") (pintype "input"))
      (node (ref "R48") (pin "2") (pinfunction "2_2") (pintype "unspecified"))
      (node (ref "U11") (pin "2") (pinfunction "C_2") (pintype "unspecified"))
    )
    (net (code "55") (name "Net-(Q4-E)") (class "Default")
      (node (ref "Q4") (pin "1") (pinfunction "E_1") (pintype "input"))
      (node (ref "R49") (pin "1") (pinfunction "1_1") (pintype "unspecified"))
    )
    (net (code "56") (name "Net-(Q5-B)") (class "Default")
      (node (ref "Q5") (pin "2") (pinfunction "B_2") (pintype "input"))
      (node (ref "R75") (pin "2") (pinfunction "2_2") (pintype "unspecified"))
    )
    (net (code "57") (name "Net-(Q6-B)") (class "Default")
      (node (ref "Q6") (pin "2") (pinfunction "B_2") (pintype "input"))
      (node (ref "R76") (pin "2") (pinfunction "2_2") (pintype "unspecified"))
    )
    (net (code "58") (name "Net-(U2-+IN)") (class "Default")
      (node (ref "C1") (pin "2") (pinfunction "2_2") (pintype "unspecified"))
      (node (ref "U2") (pin "2") (pinfunction "BYPASS_2") (pintype "unspecified"))
      (node (ref "U2") (pin "3") (pinfunction "+IN_3") (pintype "unspecified"))
    )
    (net (code "59") (name "Net-(U2--IN)") (class "Default")
      (node (ref "R13") (pin "2") (pinfunction "2_2") (pintype "unspecified"))
      (node (ref "R14") (pin "1") (pinfunction "1_1") (pintype "unspecified"))
      (node (ref "U2") (pin "4") (pinfunction "-IN_4") (pintype "unspecified"))
    )
    (net (code "60") (name "Net-(U2-VO1)") (class "Default")
      (node (ref "R14") (pin "2") (pinfunction "2_2") (pintype "unspecified"))
      (node (ref "SP1") (pin "+") (pinfunction "+_+") (pintype "unspecified"))
      (node (ref "U2") (pin "5") (pinfunction "VO1_5") (pintype "unspecified"))
    )
    (net (code "61") (name "Net-(U2-VO2)") (class "Default")
      (node (ref "SP1") (pin "-") (pinfunction "-_-") (pintype "unspecified"))
      (node (ref "U2") (pin "8") (pinfunction "VO2_8") (pintype "unspecified"))
    )
    (net (code "62") (name "Net-(U4-CE)") (class "Default")
      (node (ref "C57") (pin "1") (pinfunction "1_1") (pintype "unspecified"))
      (node (ref "F2") (pin "1") (pinfunction "1_1") (pintype "unspecified"))
      (node (ref "R58") (pin "2") (pinfunction "2_2") (pintype "unspecified"))
      (node (ref "R59") (pin "2") (pinfunction "2_2") (pintype "unspecified"))
      (node (ref "U4") (pin "4") (pinfunction "VCC_4") (pintype "unspecified"))
      (node (ref "U4") (pin "8") (pinfunction "CE_8") (pintype "unspecified"))
    )
    (net (code "63") (name "Net-(U4-PROG)") (class "Default")
      (node (ref "R60") (pin "1") (pinfunction "1_1") (pintype "unspecified"))
      (node (ref "U4") (pin "2") (pinfunction "PROG_2") (pintype "unspecified"))
    )
    (net (code "64") (name "Net-(U5-D+)") (class "Default")
      (node (ref "U5") (pin "5") (pinfunction "D+_5") (pintype "unspecified"))
      (node (ref "USB2") (pin "A6") (pinfunction "DP1_A6") (pintype "unspecified"))
      (node (ref "USB2") (pin "B6") (pinfunction "DP2_B6") (pintype "unspecified"))
    )
    (net (code "65") (name "Net-(U5-D-)") (class "Default")
      (node (ref "U5") (pin "6") (pinfunction "D-_6") (pintype "unspecified"))
      (node (ref "USB2") (pin "A7") (pinfunction "DN1_A7") (pintype "unspecified"))
      (node (ref "USB2") (pin "B7") (pinfunction "DN2_B7") (pintype "unspecified"))
    )
    (net (code "66") (name "Net-(U5-RXD)") (class "Default")
      (node (ref "R18") (pin "2") (pinfunction "2_2") (pintype "unspecified"))
      (node (ref "U5") (pin "3") (pinfunction "RXD_3") (pintype "unspecified"))
    )
    (net (code "67") (name "Net-(U5-TXD)") (class "Default")
      (node (ref "R17") (pin "2") (pinfunction "2_2") (pintype "unspecified"))
      (node (ref "U5") (pin "2") (pinfunction "TXD_2") (pintype "unspecified"))
    )
    (net (code "68") (name "Net-(U6-CPOUT)") (class "Default")
      (node (ref "C25") (pin "1") (pinfunction "1_1") (pintype "unspecified"))
      (node (ref "U6") (pin "20") (pinfunction "CPOUT_20") (pintype "unspecified"))
    )
    (net (code "69") (name "Net-(U6-REGOUT)") (class "Default")
      (node (ref "C26") (pin "2") (pinfunction "2_2") (pintype "unspecified"))
      (node (ref "U6") (pin "10") (pinfunction "REGOUT_10") (pintype "unspecified"))
    )
    (net (code "70") (name "Net-(U7-R)") (class "Default")
      (node (ref "R29") (pin "2") (pinfunction "2_2") (pintype "unspecified"))
      (node (ref "R30") (pin "1") (pinfunction "1_1") (pintype "unspecified"))
      (node (ref "U7") (pin "1") (pinfunction "R_1") (pintype "unspecified"))
    )
    (net (code "71") (name "Net-(U8-CE)") (class "Default")
      (node (ref "C10") (pin "1") (pinfunction "1_1") (pintype "unspecified"))
      (node (ref "F1") (pin "1") (pinfunction "1_1") (pintype "unspecified"))
      (node (ref "R20") (pin "2") (pinfunction "2_2") (pintype "unspecified"))
      (node (ref "R21") (pin "2") (pinfunction "2_2") (pintype "unspecified"))
      (node (ref "U8") (pin "4") (pinfunction "VCC_4") (pintype "unspecified"))
      (node (ref "U8") (pin "8") (pinfunction "CE_8") (pintype "unspecified"))
    )
    (net (code "72") (name "Net-(U8-GND)") (class "Default")
      (node (ref "U8") (pin "1") (pinfunction "TEMP_1") (pintype "unspecified"))
      (node (ref "U8") (pin "3") (pinfunction "GND_3") (pintype "unspecified"))
    )
    (net (code "73") (name "Net-(U8-PROG)") (class "Default")
      (node (ref "R19") (pin "1") (pinfunction "1_1") (pintype "unspecified"))
      (node (ref "U8") (pin "2") (pinfunction "PROG_2") (pintype "unspecified"))
    )
    (net (code "74") (name "Net-(U9-CPOUT)") (class "Default")
      (node (ref "C37") (pin "1") (pinfunction "1_1") (pintype "unspecified"))
      (node (ref "U9") (pin "20") (pinfunction "CPOUT_20") (pintype "unspecified"))
    )
    (net (code "75") (name "Net-(U9-REGOUT)") (class "Default")
      (node (ref "C36") (pin "2") (pinfunction "2_2") (pintype "unspecified"))
      (node (ref "U9") (pin "10") (pinfunction "REGOUT_10") (pintype "unspecified"))
    )
    (net (code "76") (name "Net-(U11-R)") (class "Default")
      (node (ref "R46") (pin "1") (pinfunction "1_1") (pintype "unspecified"))
      (node (ref "R47") (pin "2") (pinfunction "2_2") (pintype "unspecified"))
      (node (ref "U11") (pin "1") (pinfunction "R_1") (pintype "unspecified"))
    )
    (net (code "77") (name "Net-(U12-D+)") (class "Default")
      (node (ref "U12") (pin "5") (pinfunction "D+_5") (pintype "unspecified"))
      (node (ref "USB1") (pin "A6") (pinfunction "DP1_A6") (pintype "unspecified"))
      (node (ref "USB1") (pin "B6") (pinfunction "DP2_B6") (pintype "unspecified"))
    )
    (net (code "78") (name "Net-(U12-D-)") (class "Default")
      (node (ref "U12") (pin "6") (pinfunction "D-_6") (pintype "unspecified"))
      (node (ref "USB1") (pin "A7") (pinfunction "DN1_A7") (pintype "unspecified"))
      (node (ref "USB1") (pin "B7") (pinfunction "DN2_B7") (pintype "unspecified"))
    )
    (net (code "79") (name "Net-(U12-RXD)") (class "Default")
      (node (ref "R56") (pin "2") (pinfunction "2_2") (pintype "unspecified"))
      (node (ref "U12") (pin "3") (pinfunction "RXD_3") (pintype "unspecified"))
    )
    (net (code "80") (name "Net-(U12-TXD)") (class "Default")
      (node (ref "R57") (pin "2") (pinfunction "2_2") (pintype "unspecified"))
      (node (ref "U12") (pin "2") (pinfunction "TXD_2") (pintype "unspecified"))
    )
    (net (code "81") (name "Net-(U13-+IN)") (class "Default")
      (node (ref "C60") (pin "2") (pinfunction "2_2") (pintype "unspecified"))
      (node (ref "U13") (pin "2") (pinfunction "BYPASS_2") (pintype "unspecified"))
      (node (ref "U13") (pin "3") (pinfunction "+IN_3") (pintype "unspecified"))
    )
    (net (code "82") (name "Net-(U13--IN)") (class "Default")
      (node (ref "R63") (pin "1") (pinfunction "1_1") (pintype "unspecified"))
      (node (ref "R64") (pin "2") (pinfunction "2_2") (pintype "unspecified"))
      (node (ref "U13") (pin "4") (pinfunction "-IN_4") (pintype "unspecified"))
    )
    (net (code "83") (name "Net-(U13-VO1)") (class "Default")
      (node (ref "R63") (pin "2") (pinfunction "2_2") (pintype "unspecified"))
      (node (ref "SP2") (pin "+") (pinfunction "+_+") (pintype "unspecified"))
      (node (ref "U13") (pin "5") (pinfunction "VO1_5") (pintype "unspecified"))
    )
    (net (code "84") (name "Net-(U13-VO2)") (class "Default")
      (node (ref "SP2") (pin "-") (pinfunction "-_-") (pintype "unspecified"))
      (node (ref "U13") (pin "8") (pinfunction "VO2_8") (pintype "unspecified"))
    )
    (net (code "85") (name "Net-(USB1-CC1)") (class "Default")
      (node (ref "R44") (pin "2") (pinfunction "2_2") (pintype "unspecified"))
      (node (ref "USB1") (pin "A5") (pinfunction "CC1_A5") (pintype "unspecified"))
    )
    (net (code "86") (name "Net-(USB1-CC2)") (class "Default")
      (node (ref "R45") (pin "2") (pinfunction "2_2") (pintype "unspecified"))
      (node (ref "USB1") (pin "B5") (pinfunction "CC2_B5") (pintype "unspecified"))
    )
    (net (code "87") (name "Net-(USB2-CC1)") (class "Default")
      (node (ref "R33") (pin "2") (pinfunction "2_2") (pintype "unspecified"))
      (node (ref "USB2") (pin "A5") (pinfunction "CC1_A5") (pintype "unspecified"))
    )
    (net (code "88") (name "Net-(USB2-CC2)") (class "Default")
      (node (ref "R32") (pin "2") (pinfunction "2_2") (pintype "unspecified"))
      (node (ref "USB2") (pin "B5") (pinfunction "CC2_B5") (pintype "unspecified"))
    )
    (net (code "89") (name "RTS") (class "Default")
      (node (ref "Q1") (pin "1") (pinfunction "E_1") (pintype "input"))
      (node (ref "Q6") (pin "1") (pinfunction "E_1") (pintype "input"))
      (node (ref "R2") (pin "1") (pinfunction "1_1") (pintype "unspecified"))
      (node (ref "R75") (pin "1") (pinfunction "1_1") (pintype "unspecified"))
      (node (ref "U12") (pin "14") (pinfunction "RTS#_14") (pintype "unspecified"))
      (node (ref "U5") (pin "14") (pinfunction "RTS#_14") (pintype "unspecified"))
    )
    (net (code "90") (name "RXD0") (class "Default")
      (node (ref "R17") (pin "1") (pinfunction "1_1") (pintype "unspecified"))
      (node (ref "R57") (pin "1") (pinfunction "1_1") (pintype "unspecified"))
      (node (ref "U1") (pin "34") (pinfunction "RXD0_34") (pintype "unspecified"))
      (node (ref "U14") (pin "34") (pinfunction "RXD0_34") (pintype "unspecified"))
    )
    (net (code "91") (name "SCL") (class "Default")
      (node (ref "R37") (pin "1") (pinfunction "1_1") (pintype "unspecified"))
      (node (ref "R40") (pin "1") (pinfunction "1_1") (pintype "unspecified"))
      (node (ref "U1") (pin "36") (pinfunction "IO22_36") (pintype "unspecified"))
      (node (ref "U14") (pin "36") (pinfunction "IO22_36") (pintype "unspecified"))
      (node (ref "U6") (pin "23") (pinfunction "SCL_23") (pintype "unspecified"))
      (node (ref "U9") (pin "23") (pinfunction "SCL_23") (pintype "unspecified"))
    )
    (net (code "92") (name "SDA") (class "Default")
      (node (ref "R38") (pin "1") (pinfunction "1_1") (pintype "unspecified"))
      (node (ref "R39") (pin "1") (pinfunction "1_1") (pintype "unspecified"))
      (node (ref "U1") (pin "33") (pinfunction "IO21_33") (pintype "unspecified"))
      (node (ref "U14") (pin "33") (pinfunction "IO21_33") (pintype "unspecified"))
      (node (ref "U6") (pin "24") (pinfunction "SDA_24") (pintype "unspecified"))
      (node (ref "U9") (pin "24") (pinfunction "SDA_24") (pintype "unspecified"))
    )
    (net (code "93") (name "TXD0") (class "Default")
      (node (ref "R18") (pin "1") (pinfunction "1_1") (pintype "unspecified"))
      (node (ref "R56") (pin "1") (pinfunction "1_1") (pintype "unspecified"))
      (node (ref "U1") (pin "35") (pinfunction "TXD0_35") (pintype "unspecified"))
      (node (ref "U14") (pin "35") (pinfunction "TXD0_35") (pintype "unspecified"))
    )
    (net (code "94") (name "VCC") (class "Default")
      (node (ref "C11") (pin "2") (pinfunction "2_2") (pintype "unspecified"))
      (node (ref "C12") (pin "2") (pinfunction "2_2") (pintype "unspecified"))
      (node (ref "C13") (pin "2") (pinfunction "2_2") (pintype "unspecified"))
      (node (ref "C14") (pin "2") (pinfunction "2_2") (pintype "unspecified"))
      (node (ref "C15") (pin "1") (pinfunction "1_1") (pintype "unspecified"))
      (node (ref "C27") (pin "2") (pinfunction "2_2") (pintype "unspecified"))
      (node (ref "C28") (pin "2") (pinfunction "2_2") (pintype "unspecified"))
      (node (ref "C34") (pin "2") (pinfunction "2_2") (pintype "unspecified"))
      (node (ref "C35") (pin "2") (pinfunction "2_2") (pintype "unspecified"))
      (node (ref "C4") (pin "1") (pinfunction "1_1") (pintype "unspecified"))
      (node (ref "C46") (pin "1") (pinfunction "1_1") (pintype "unspecified"))
      (node (ref "C49") (pin "1") (pinfunction "1_1") (pintype "unspecified"))
      (node (ref "C51") (pin "2") (pinfunction "2_2") (pintype "unspecified"))
      (node (ref "C52") (pin "2") (pinfunction "2_2") (pintype "unspecified"))
      (node (ref "C53") (pin "2") (pinfunction "2_2") (pintype "unspecified"))
      (node (ref "C54") (pin "2") (pinfunction "2_2") (pintype "unspecified"))
      (node (ref "C55") (pin "2") (pinfunction "2_2") (pintype "unspecified"))
      (node (ref "C56") (pin "2") (pinfunction "2_2") (pintype "unspecified"))
      (node (ref "C7") (pin "2") (pinfunction "2_2") (pintype "unspecified"))
      (node (ref "C8") (pin "2") (pinfunction "2_2") (pintype "unspecified"))
      (node (ref "LCD") (pin "10") (pinfunction "LED-A_10") (pintype "unspecified"))
      (node (ref "LCD") (pin "9") (pinfunction "VCC_9") (pintype "unspecified"))
      (node (ref "LCD1") (pin "10") (pinfunction "LED-A_10") (pintype "unspecified"))
      (node (ref "LCD1") (pin "9") (pinfunction "VCC_9") (pintype "unspecified"))
      (node (ref "R10") (pin "1") (pinfunction "1_1") (pintype "unspecified"))
      (node (ref "R11") (pin "1") (pinfunction "1_1") (pintype "unspecified"))
      (node (ref "R12") (pin "1") (pinfunction "1_1") (pintype "unspecified"))
      (node (ref "R23") (pin "1") (pinfunction "1_1") (pintype "unspecified"))
      (node (ref "R24") (pin "1") (pinfunction "1_1") (pintype "unspecified"))
      (node (ref "R25") (pin "1") (pinfunction "1_1") (pintype "unspecified"))
      (node (ref "R26") (pin "1") (pinfunction "1_1") (pintype "unspecified"))
      (node (ref "R35") (pin "1") (pinfunction "1_1") (pintype "unspecified"))
      (node (ref "R36") (pin "1") (pinfunction "1_1") (pintype "unspecified"))
      (node (ref "R37") (pin "2") (pinfunction "2_2") (pintype "unspecified"))
      (node (ref "R38") (pin "2") (pinfunction "2_2") (pintype "unspecified"))
      (node (ref "R39") (pin "2") (pinfunction "2_2") (pintype "unspecified"))
      (node (ref "R40") (pin "2") (pinfunction "2_2") (pintype "unspecified"))
      (node (ref "R41") (pin "1") (pinfunction "1_1") (pintype "unspecified"))
      (node (ref "R42") (pin "1") (pinfunction "1_1") (pintype "unspecified"))
      (node (ref "R51") (pin "1") (pinfunction "1_1") (pintype "unspecified"))
      (node (ref "R52") (pin "1") (pinfunction "1_1") (pintype "unspecified"))
      (node (ref "R53") (pin "1") (pinfunction "1_1") (pintype "unspecified"))
      (node (ref "R54") (pin "1") (pinfunction "1_1") (pintype "unspecified"))
      (node (ref "R65") (pin "1") (pinfunction "1_1") (pintype "unspecified"))
      (node (ref "R66") (pin "1") (pinfunction "1_1") (pintype "unspecified"))
      (node (ref "R67") (pin "1") (pinfunction "1_1") (pintype "unspecified"))
      (node (ref "R68") (pin "1") (pinfunction "1_1") (pintype "unspecified"))
      (node (ref "R69") (pin "1") (pinfunction "1_1") (pintype "unspecified"))
      (node (ref "R7") (pin "1") (pinfunction "1_1") (pintype "unspecified"))
      (node (ref "R70") (pin "1") (pinfunction "1_1") (pintype "unspecified"))
      (node (ref "R8") (pin "1") (pinfunction "1_1") (pintype "unspecified"))
      (node (ref "R9") (pin "1") (pinfunction "1_1") (pintype "unspecified"))
      (node (ref "U1") (pin "2") (pinfunction "3V3_2") (pintype "unspecified"))
      (node (ref "U10") (pin "2") (pinfunction "Output_2") (pintype "unspecified"))
      (node (ref "U10") (pin "4") (pinfunction "Output_4") (pintype "unspecified"))
      (node (ref "U12") (pin "16") (pinfunction "VCC_16") (pintype "unspecified"))
      (node (ref "U12") (pin "4") (pinfunction "V3_4") (pintype "unspecified"))
      (node (ref "U14") (pin "2") (pinfunction "3V3_2") (pintype "unspecified"))
      (node (ref "U3") (pin "2") (pinfunction "Output_2") (pintype "unspecified"))
      (node (ref "U3") (pin "4") (pinfunction "Output_4") (pintype "unspecified"))
      (node (ref "U5") (pin "16") (pinfunction "VCC_16") (pintype "unspecified"))
      (node (ref "U5") (pin "4") (pinfunction "V3_4") (pintype "unspecified"))
      (node (ref "U6") (pin "13") (pinfunction "VDD_13") (pintype "unspecified"))
      (node (ref "U6") (pin "8") (pinfunction "VLOGIC_8") (pintype "unspecified"))
      (node (ref "U9") (pin "13") (pinfunction "VDD_13") (pintype "unspecified"))
      (node (ref "U9") (pin "8") (pinfunction "VLOGIC_8") (pintype "unspecified"))
    )
    (net (code "95") (name "VDD_5V") (class "Default")
      (node (ref "C3") (pin "2") (pinfunction "2_2") (pintype "unspecified"))
      (node (ref "C47") (pin "1") (pinfunction "1_1") (pintype "unspecified"))
      (node (ref "C48") (pin "1") (pinfunction "1_1") (pintype "unspecified"))
      (node (ref "C5") (pin "1") (pinfunction "1_1") (pintype "unspecified"))
      (node (ref "C58") (pin "2") (pinfunction "2_2") (pintype "unspecified"))
      (node (ref "C6") (pin "1") (pinfunction "1_1") (pintype "unspecified"))
      (node (ref "R34") (pin "2") (pinfunction "2_2") (pintype "unspecified"))
      (node (ref "R43") (pin "2") (pinfunction "2_2") (pintype "unspecified"))
      (node (ref "SW1") (pin "1") (pinfunction "1_1") (pintype "unspecified"))
      (node (ref "SW3") (pin "1") (pinfunction "1_1") (pintype "unspecified"))
      (node (ref "U10") (pin "3") (pinfunction "Input_3") (pintype "unspecified"))
      (node (ref "U13") (pin "6") (pinfunction "VDD_6") (pintype "unspecified"))
      (node (ref "U2") (pin "6") (pinfunction "VDD_6") (pintype "unspecified"))
      (node (ref "U3") (pin "3") (pinfunction "Input_3") (pintype "unspecified"))
    )
    (net (code "96") (name "unconnected-(LCD-SDO-Pad7)") (class "Default")
      (node (ref "LCD") (pin "7") (pinfunction "SDO_7") (pintype "unspecified+no_connect"))
    )
    (net (code "97") (name "unconnected-(LCD-XL-Pad15)") (class "Default")
      (node (ref "LCD") (pin "15") (pinfunction "XL_15") (pintype "unspecified+no_connect"))
    )
    (net (code "98") (name "unconnected-(LCD-XR-Pad17)") (class "Default")
      (node (ref "LCD") (pin "17") (pinfunction "XR_17") (pintype "unspecified+no_connect"))
    )
    (net (code "99") (name "unconnected-(LCD-YD-Pad18)") (class "Default")
      (node (ref "LCD") (pin "18") (pinfunction "YD_18") (pintype "unspecified+no_connect"))
    )
    (net (code "100") (name "unconnected-(LCD-YU-Pad16)") (class "Default")
      (node (ref "LCD") (pin "16") (pinfunction "YU_16") (pintype "unspecified+no_connect"))
    )
    (net (code "101") (name "unconnected-(LCD1-SDO-Pad7)") (class "Default")
      (node (ref "LCD1") (pin "7") (pinfunction "SDO_7") (pintype "unspecified+no_connect"))
    )
    (net (code "102") (name "unconnected-(LCD1-XL-Pad15)") (class "Default")
      (node (ref "LCD1") (pin "15") (pinfunction "XL_15") (pintype "unspecified+no_connect"))
    )
    (net (code "103") (name "unconnected-(LCD1-XR-Pad17)") (class "Default")
      (node (ref "LCD1") (pin "17") (pinfunction "XR_17") (pintype "unspecified+no_connect"))
    )
    (net (code "104") (name "unconnected-(LCD1-YD-Pad18)") (class "Default")
      (node (ref "LCD1") (pin "18") (pinfunction "YD_18") (pintype "unspecified+no_connect"))
    )
    (net (code "105") (name "unconnected-(LCD1-YU-Pad16)") (class "Default")
      (node (ref "LCD1") (pin "16") (pinfunction "YU_16") (pintype "unspecified+no_connect"))
    )
    (net (code "106") (name "unconnected-(R22-EH-Pad6)") (class "Default")
      (node (ref "R22") (pin "6") (pinfunction "EH_6") (pintype "unspecified+no_connect"))
    )
    (net (code "107") (name "unconnected-(R22-EH-Pad7)") (class "Default")
      (node (ref "R22") (pin "7") (pinfunction "EH_7") (pintype "unspecified+no_connect"))
    )
    (net (code "108") (name "unconnected-(R22-Pad2)") (class "Default")
      (node (ref "R22") (pin "2") (pinfunction "2_2") (pintype "unspecified+no_connect"))
    )
    (net (code "109") (name "unconnected-(R22-Pad3)") (class "Default")
      (node (ref "R22") (pin "3") (pinfunction "3_3") (pintype "unspecified+no_connect"))
    )
    (net (code "110") (name "unconnected-(R55-EH-Pad6)") (class "Default")
      (node (ref "R55") (pin "6") (pinfunction "EH_6") (pintype "unspecified+no_connect"))
    )
    (net (code "111") (name "unconnected-(R55-EH-Pad7)") (class "Default")
      (node (ref "R55") (pin "7") (pinfunction "EH_7") (pintype "unspecified+no_connect"))
    )
    (net (code "112") (name "unconnected-(R55-Pad2)") (class "Default")
      (node (ref "R55") (pin "2") (pinfunction "2_2") (pintype "unspecified+no_connect"))
    )
    (net (code "113") (name "unconnected-(R55-Pad3)") (class "Default")
      (node (ref "R55") (pin "3") (pinfunction "3_3") (pintype "unspecified+no_connect"))
    )
    (net (code "114") (name "unconnected-(U1-CLK-Pad20)") (class "Default")
      (node (ref "U1") (pin "20") (pinfunction "CLK_20") (pintype "unspecified+no_connect"))
    )
    (net (code "115") (name "unconnected-(U1-CMD-Pad19)") (class "Default")
      (node (ref "U1") (pin "19") (pinfunction "CMD_19") (pintype "unspecified+no_connect"))
    )
    (net (code "116") (name "unconnected-(U1-IO15-Pad23)") (class "Default")
      (node (ref "U1") (pin "23") (pinfunction "IO15_23") (pintype "unspecified+no_connect"))
    )
    (net (code "117") (name "unconnected-(U1-IO19-Pad31)") (class "Default")
      (node (ref "U1") (pin "31") (pinfunction "IO19_31") (pintype "unspecified+no_connect"))
    )
    (net (code "118") (name "unconnected-(U1-NC-Pad32)") (class "Default")
      (node (ref "U1") (pin "32") (pinfunction "NC_32") (pintype "unspecified+no_connect"))
    )
    (net (code "119") (name "unconnected-(U1-SD0-Pad21)") (class "Default")
      (node (ref "U1") (pin "21") (pinfunction "SD0_21") (pintype "unspecified+no_connect"))
    )
    (net (code "120") (name "unconnected-(U1-SD1-Pad22)") (class "Default")
      (node (ref "U1") (pin "22") (pinfunction "SD1_22") (pintype "unspecified+no_connect"))
    )
    (net (code "121") (name "unconnected-(U1-SD2-Pad17)") (class "Default")
      (node (ref "U1") (pin "17") (pinfunction "SD2_17") (pintype "unspecified+no_connect"))
    )
    (net (code "122") (name "unconnected-(U1-SD3-Pad18)") (class "Default")
      (node (ref "U1") (pin "18") (pinfunction "SD3_18") (pintype "unspecified+no_connect"))
    )
    (net (code "123") (name "unconnected-(U1-SENSOR_VN-Pad5)") (class "Default")
      (node (ref "U1") (pin "5") (pinfunction "SENSOR_VN_5") (pintype "unspecified+no_connect"))
    )
    (net (code "124") (name "unconnected-(U1-SENSOR_VP-Pad4)") (class "Default")
      (node (ref "U1") (pin "4") (pinfunction "SENSOR_VP_4") (pintype "unspecified+no_connect"))
    )
    (net (code "125") (name "unconnected-(U5-CTS#-Pad9)") (class "Default")
      (node (ref "U5") (pin "9") (pinfunction "CTS#_9") (pintype "unspecified+no_connect"))
    )
    (net (code "126") (name "unconnected-(U5-DCD#-Pad12)") (class "Default")
      (node (ref "U5") (pin "12") (pinfunction "DCD#_12") (pintype "unspecified+no_connect"))
    )
    (net (code "127") (name "unconnected-(U5-DSR#-Pad10)") (class "Default")
      (node (ref "U5") (pin "10") (pinfunction "DSR#_10") (pintype "unspecified+no_connect"))
    )
    (net (code "128") (name "unconnected-(U5-NC.-Pad7)") (class "Default")
      (node (ref "U5") (pin "7") (pinfunction "NC._7") (pintype "unspecified+no_connect"))
    )
    (net (code "129") (name "unconnected-(U5-NC.-Pad8)") (class "Default")
      (node (ref "U5") (pin "8") (pinfunction "NC._8") (pintype "unspecified+no_connect"))
    )
    (net (code "130") (name "unconnected-(U5-R232-Pad15)") (class "Default")
      (node (ref "U5") (pin "15") (pinfunction "R232_15") (pintype "unspecified+no_connect"))
    )
    (net (code "131") (name "unconnected-(U5-RI#-Pad11)") (class "Default")
      (node (ref "U5") (pin "11") (pinfunction "RI#_11") (pintype "unspecified+no_connect"))
    )
    (net (code "132") (name "unconnected-(U6-AUX_CL-Pad7)") (class "Default")
      (node (ref "U6") (pin "7") (pinfunction "AUX_CL_7") (pintype "unspecified+no_connect"))
    )
    (net (code "133") (name "unconnected-(U6-AUX_DA-Pad6)") (class "Default")
      (node (ref "U6") (pin "6") (pinfunction "AUX_DA_6") (pintype "unspecified+no_connect"))
    )
    (net (code "134") (name "unconnected-(U6-INT-Pad12)") (class "Default")
      (node (ref "U6") (pin "12") (pinfunction "INT_12") (pintype "unspecified+no_connect"))
    )
    (net (code "135") (name "unconnected-(U6-RESV-Pad19)") (class "Default")
      (node (ref "U6") (pin "19") (pinfunction "RESV_19") (pintype "unspecified+no_connect"))
    )
    (net (code "136") (name "unconnected-(U6-RESV-Pad21)") (class "Default")
      (node (ref "U6") (pin "21") (pinfunction "RESV_21") (pintype "unspecified+no_connect"))
    )
    (net (code "137") (name "unconnected-(U6-RESV-Pad22)") (class "Default")
      (node (ref "U6") (pin "22") (pinfunction "RESV_22") (pintype "unspecified+no_connect"))
    )
    (net (code "138") (name "unconnected-(U9-AUX_CL-Pad7)") (class "Default")
      (node (ref "U9") (pin "7") (pinfunction "AUX_CL_7") (pintype "unspecified+no_connect"))
    )
    (net (code "139") (name "unconnected-(U9-AUX_DA-Pad6)") (class "Default")
      (node (ref "U9") (pin "6") (pinfunction "AUX_DA_6") (pintype "unspecified+no_connect"))
    )
    (net (code "140") (name "unconnected-(U9-INT-Pad12)") (class "Default")
      (node (ref "U9") (pin "12") (pinfunction "INT_12") (pintype "unspecified+no_connect"))
    )
    (net (code "141") (name "unconnected-(U9-RESV-Pad19)") (class "Default")
      (node (ref "U9") (pin "19") (pinfunction "RESV_19") (pintype "unspecified+no_connect"))
    )
    (net (code "142") (name "unconnected-(U9-RESV-Pad21)") (class "Default")
      (node (ref "U9") (pin "21") (pinfunction "RESV_21") (pintype "unspecified+no_connect"))
    )
    (net (code "143") (name "unconnected-(U9-RESV-Pad22)") (class "Default")
      (node (ref "U9") (pin "22") (pinfunction "RESV_22") (pintype "unspecified+no_connect"))
    )
    (net (code "144") (name "unconnected-(U12-CTS#-Pad9)") (class "Default")
      (node (ref "U12") (pin "9") (pinfunction "CTS#_9") (pintype "unspecified+no_connect"))
    )
    (net (code "145") (name "unconnected-(U12-DCD#-Pad12)") (class "Default")
      (node (ref "U12") (pin "12") (pinfunction "DCD#_12") (pintype "unspecified+no_connect"))
    )
    (net (code "146") (name "unconnected-(U12-DSR#-Pad10)") (class "Default")
      (node (ref "U12") (pin "10") (pinfunction "DSR#_10") (pintype "unspecified+no_connect"))
    )
    (net (code "147") (name "unconnected-(U12-NC.-Pad7)") (class "Default")
      (node (ref "U12") (pin "7") (pinfunction "NC._7") (pintype "unspecified+no_connect"))
    )
    (net (code "148") (name "unconnected-(U12-NC.-Pad8)") (class "Default")
      (node (ref "U12") (pin "8") (pinfunction "NC._8") (pintype "unspecified+no_connect"))
    )
    (net (code "149") (name "unconnected-(U12-R232-Pad15)") (class "Default")
      (node (ref "U12") (pin "15") (pinfunction "R232_15") (pintype "unspecified+no_connect"))
    )
    (net (code "150") (name "unconnected-(U12-RI#-Pad11)") (class "Default")
      (node (ref "U12") (pin "11") (pinfunction "RI#_11") (pintype "unspecified+no_connect"))
    )
    (net (code "151") (name "unconnected-(U14-CLK-Pad20)") (class "Default")
      (node (ref "U14") (pin "20") (pinfunction "CLK_20") (pintype "unspecified+no_connect"))
    )
    (net (code "152") (name "unconnected-(U14-CMD-Pad19)") (class "Default")
      (node (ref "U14") (pin "19") (pinfunction "CMD_19") (pintype "unspecified+no_connect"))
    )
    (net (code "153") (name "unconnected-(U14-IO12-Pad14)") (class "Default")
      (node (ref "U14") (pin "14") (pinfunction "IO12_14") (pintype "unspecified+no_connect"))
    )
    (net (code "154") (name "unconnected-(U14-IO15-Pad23)") (class "Default")
      (node (ref "U14") (pin "23") (pinfunction "IO15_23") (pintype "unspecified+no_connect"))
    )
    (net (code "155") (name "unconnected-(U14-NC-Pad32)") (class "Default")
      (node (ref "U14") (pin "32") (pinfunction "NC_32") (pintype "unspecified+no_connect"))
    )
    (net (code "156") (name "unconnected-(U14-SD0-Pad21)") (class "Default")
      (node (ref "U14") (pin "21") (pinfunction "SD0_21") (pintype "unspecified+no_connect"))
    )
    (net (code "157") (name "unconnected-(U14-SD1-Pad22)") (class "Default")
      (node (ref "U14") (pin "22") (pinfunction "SD1_22") (pintype "unspecified+no_connect"))
    )
    (net (code "158") (name "unconnected-(U14-SD2-Pad17)") (class "Default")
      (node (ref "U14") (pin "17") (pinfunction "SD2_17") (pintype "unspecified+no_connect"))
    )
    (net (code "159") (name "unconnected-(U14-SD3-Pad18)") (class "Default")
      (node (ref "U14") (pin "18") (pinfunction "SD3_18") (pintype "unspecified+no_connect"))
    )
    (net (code "160") (name "unconnected-(U14-SENSOR_VN-Pad5)") (class "Default")
      (node (ref "U14") (pin "5") (pinfunction "SENSOR_VN_5") (pintype "unspecified+no_connect"))
    )
    (net (code "161") (name "unconnected-(U14-SENSOR_VP-Pad4)") (class "Default")
      (node (ref "U14") (pin "4") (pinfunction "SENSOR_VP_4") (pintype "unspecified+no_connect"))
    )
    (net (code "162") (name "unconnected-(USB1-SBU1-PadA8)") (class "Default")
      (node (ref "USB1") (pin "A8") (pinfunction "SBU1_A8") (pintype "unspecified+no_connect"))
    )
    (net (code "163") (name "unconnected-(USB1-SBU2-PadB8)") (class "Default")
      (node (ref "USB1") (pin "B8") (pinfunction "SBU2_B8") (pintype "unspecified+no_connect"))
    )
    (net (code "164") (name "unconnected-(USB2-SBU1-PadA8)") (class "Default")
      (node (ref "USB2") (pin "A8") (pinfunction "SBU1_A8") (pintype "unspecified+no_connect"))
    )
    (net (code "165") (name "unconnected-(USB2-SBU2-PadB8)") (class "Default")
      (node (ref "USB2") (pin "B8") (pinfunction "SBU2_B8") (pintype "unspecified+no_connect"))
    )
  )
)
